# XMICRO-BP8.net
KiCad netlist of a schematic drawn in EAGLE
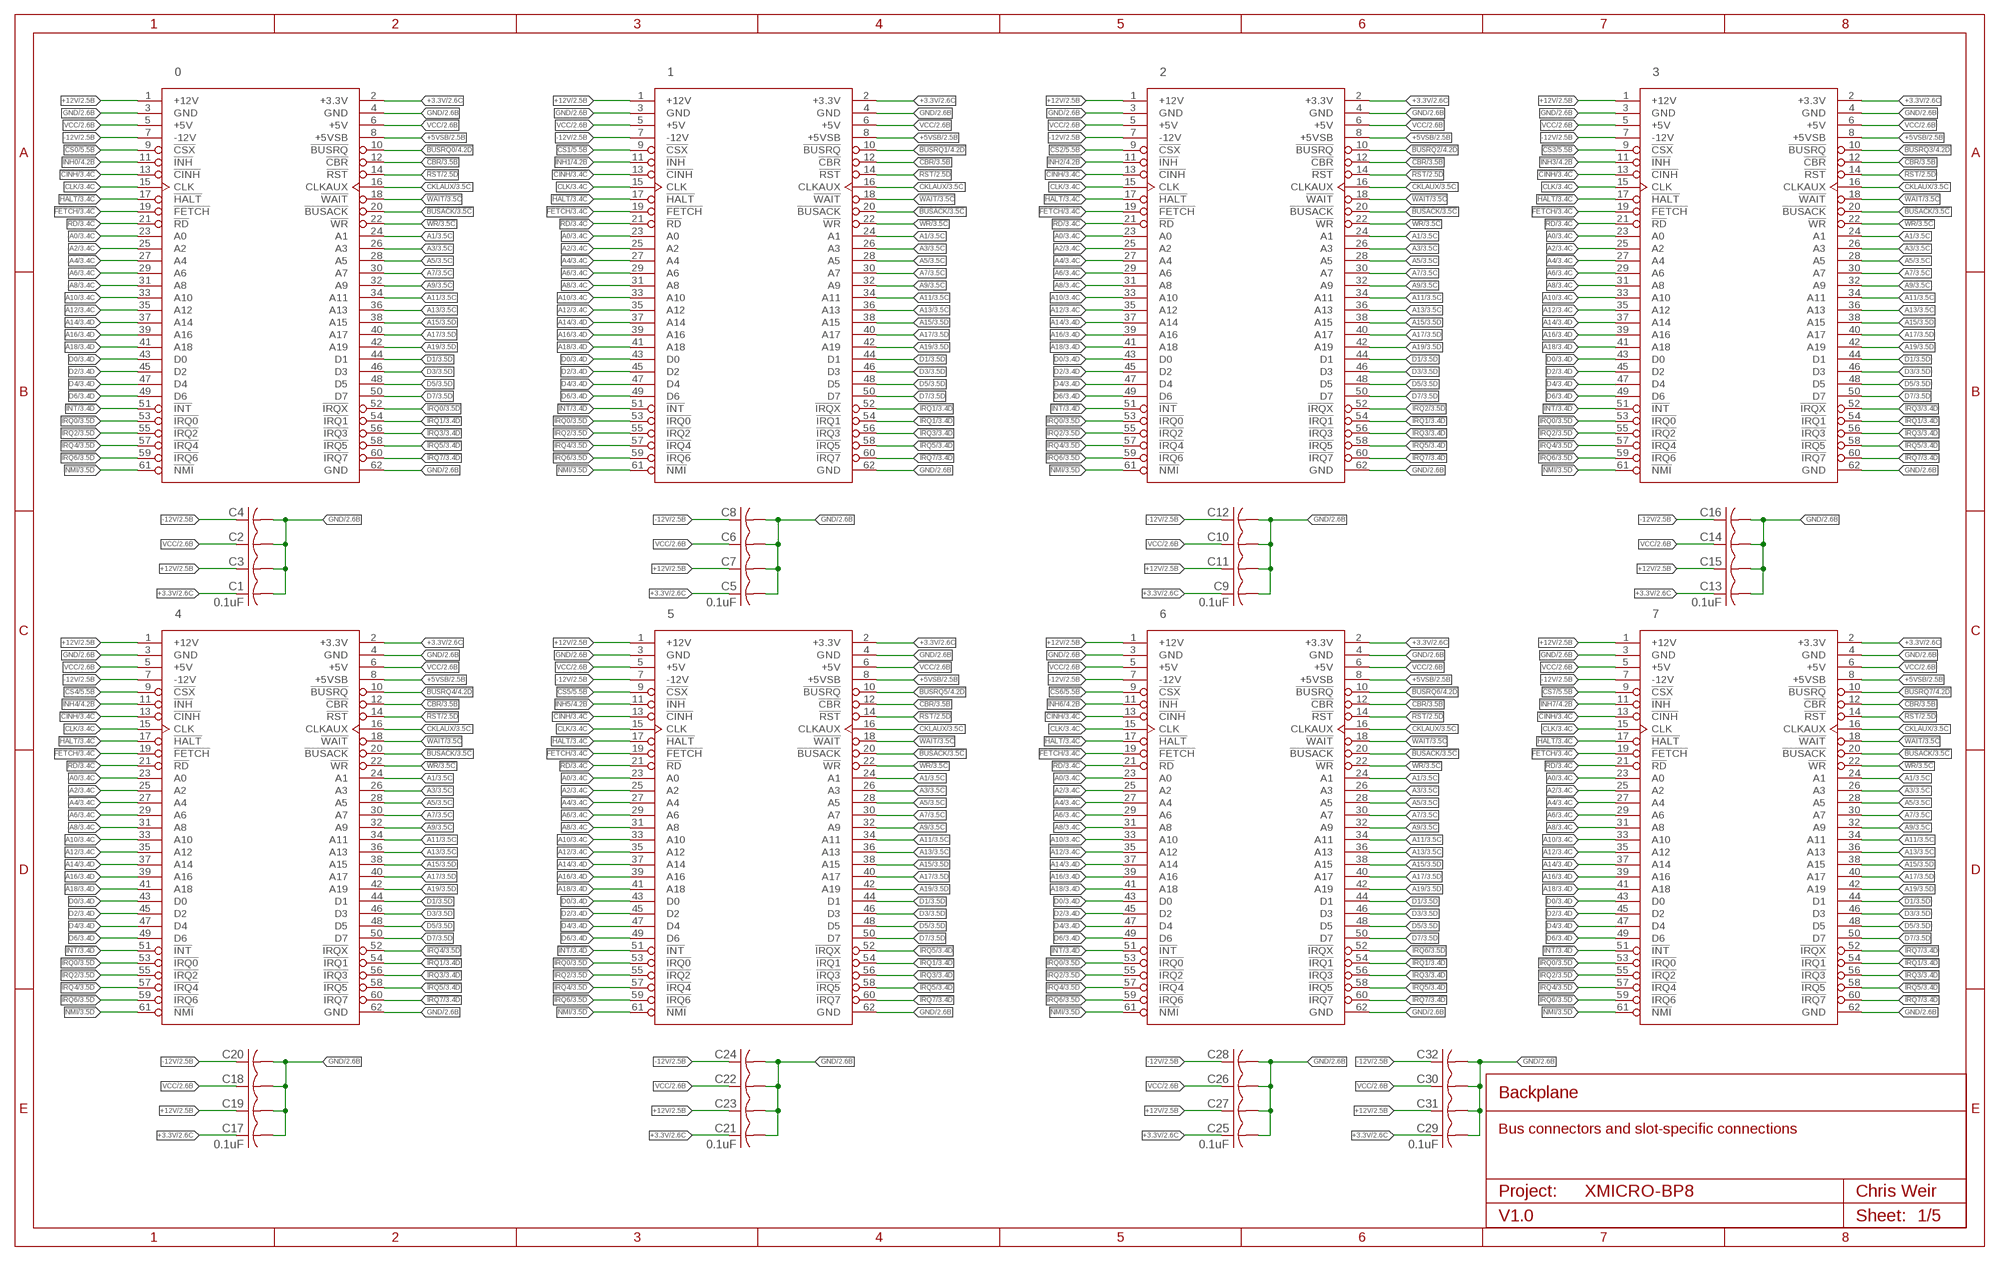
[diagram p0: schematic, sheet 1]
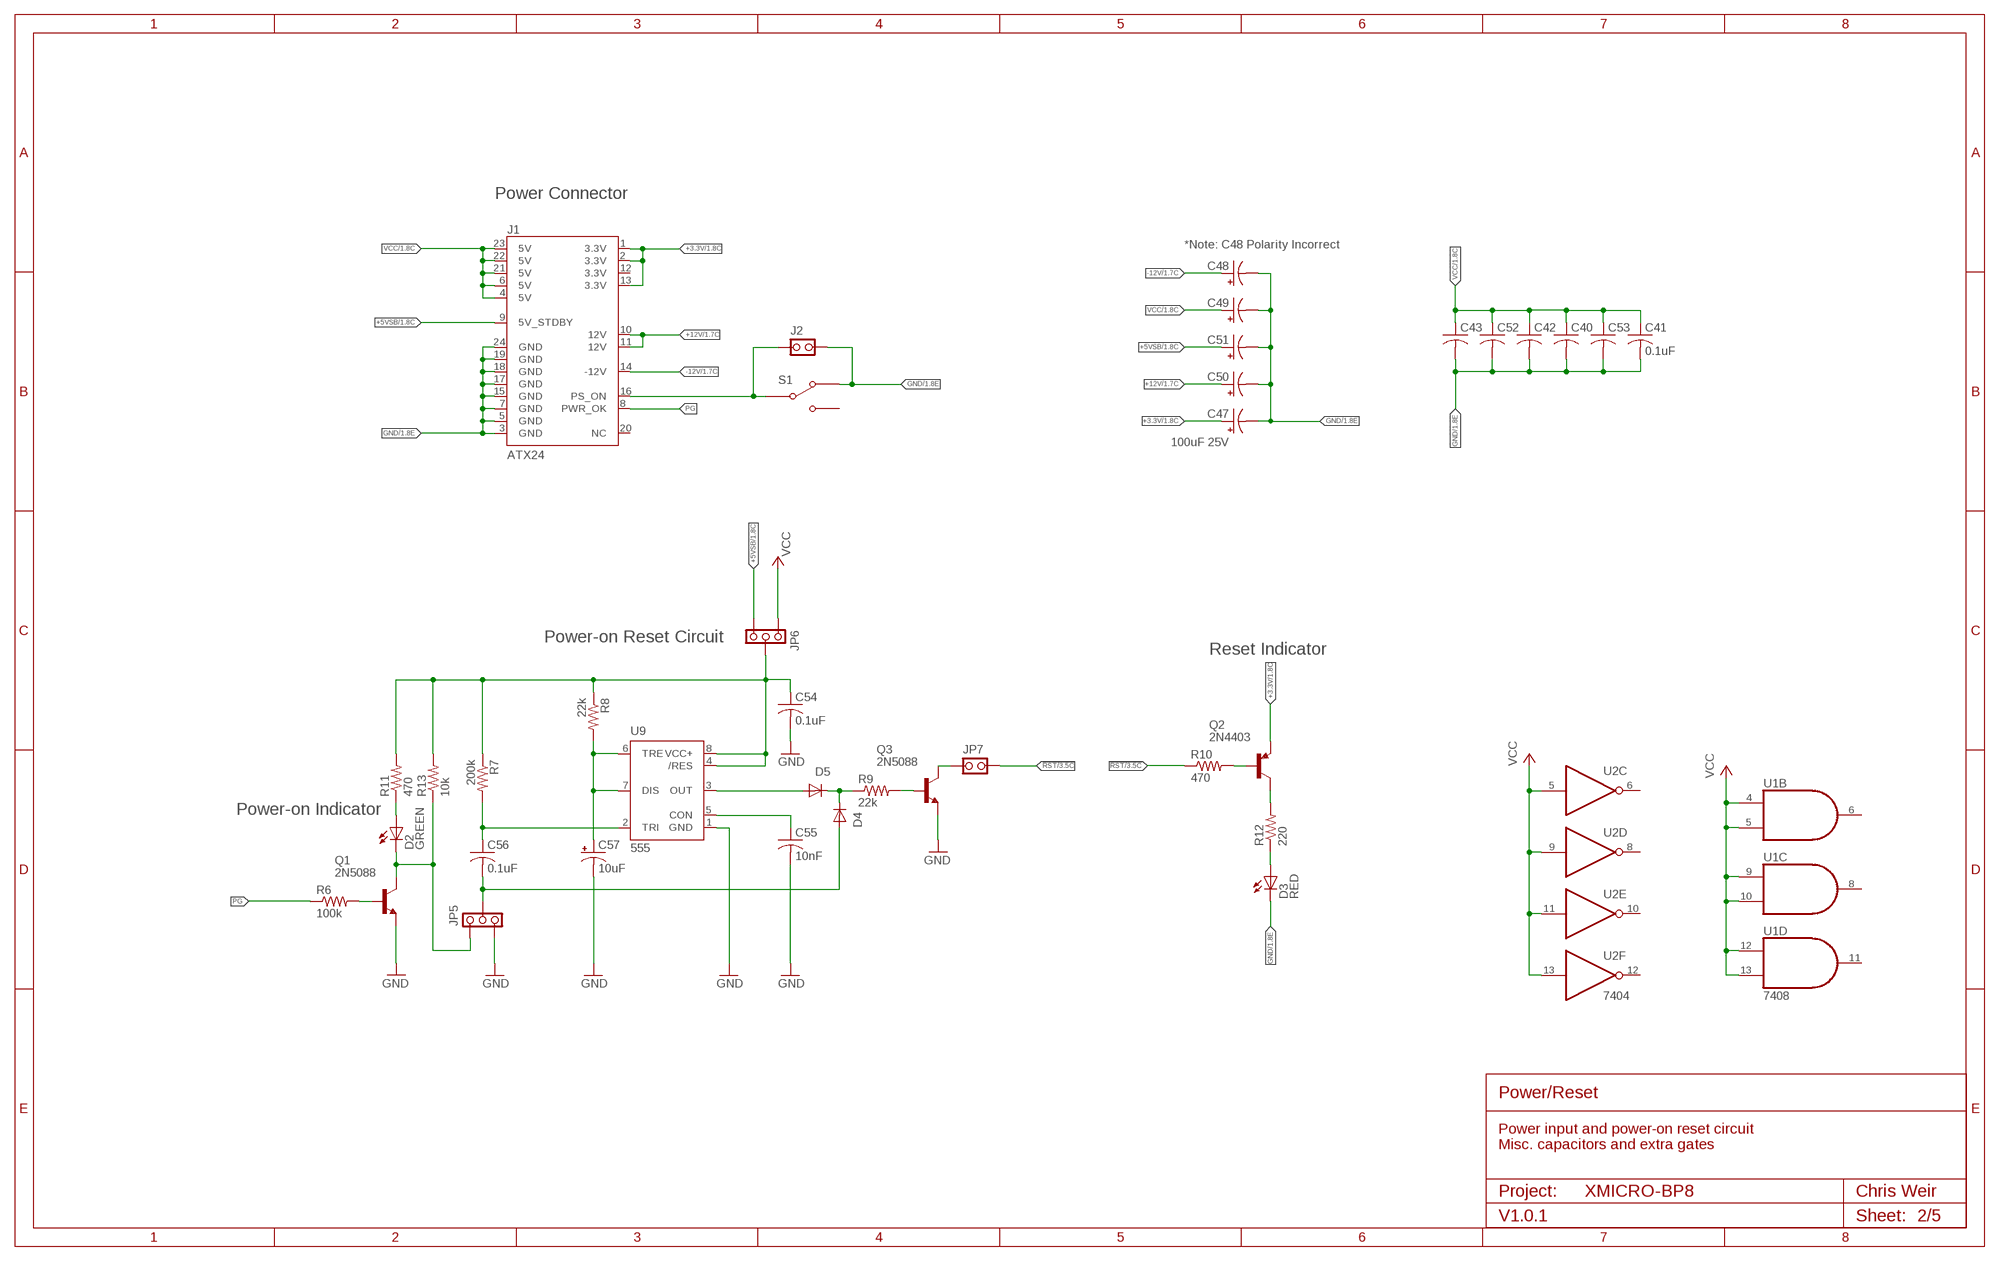
[diagram p1: schematic, sheet 2]
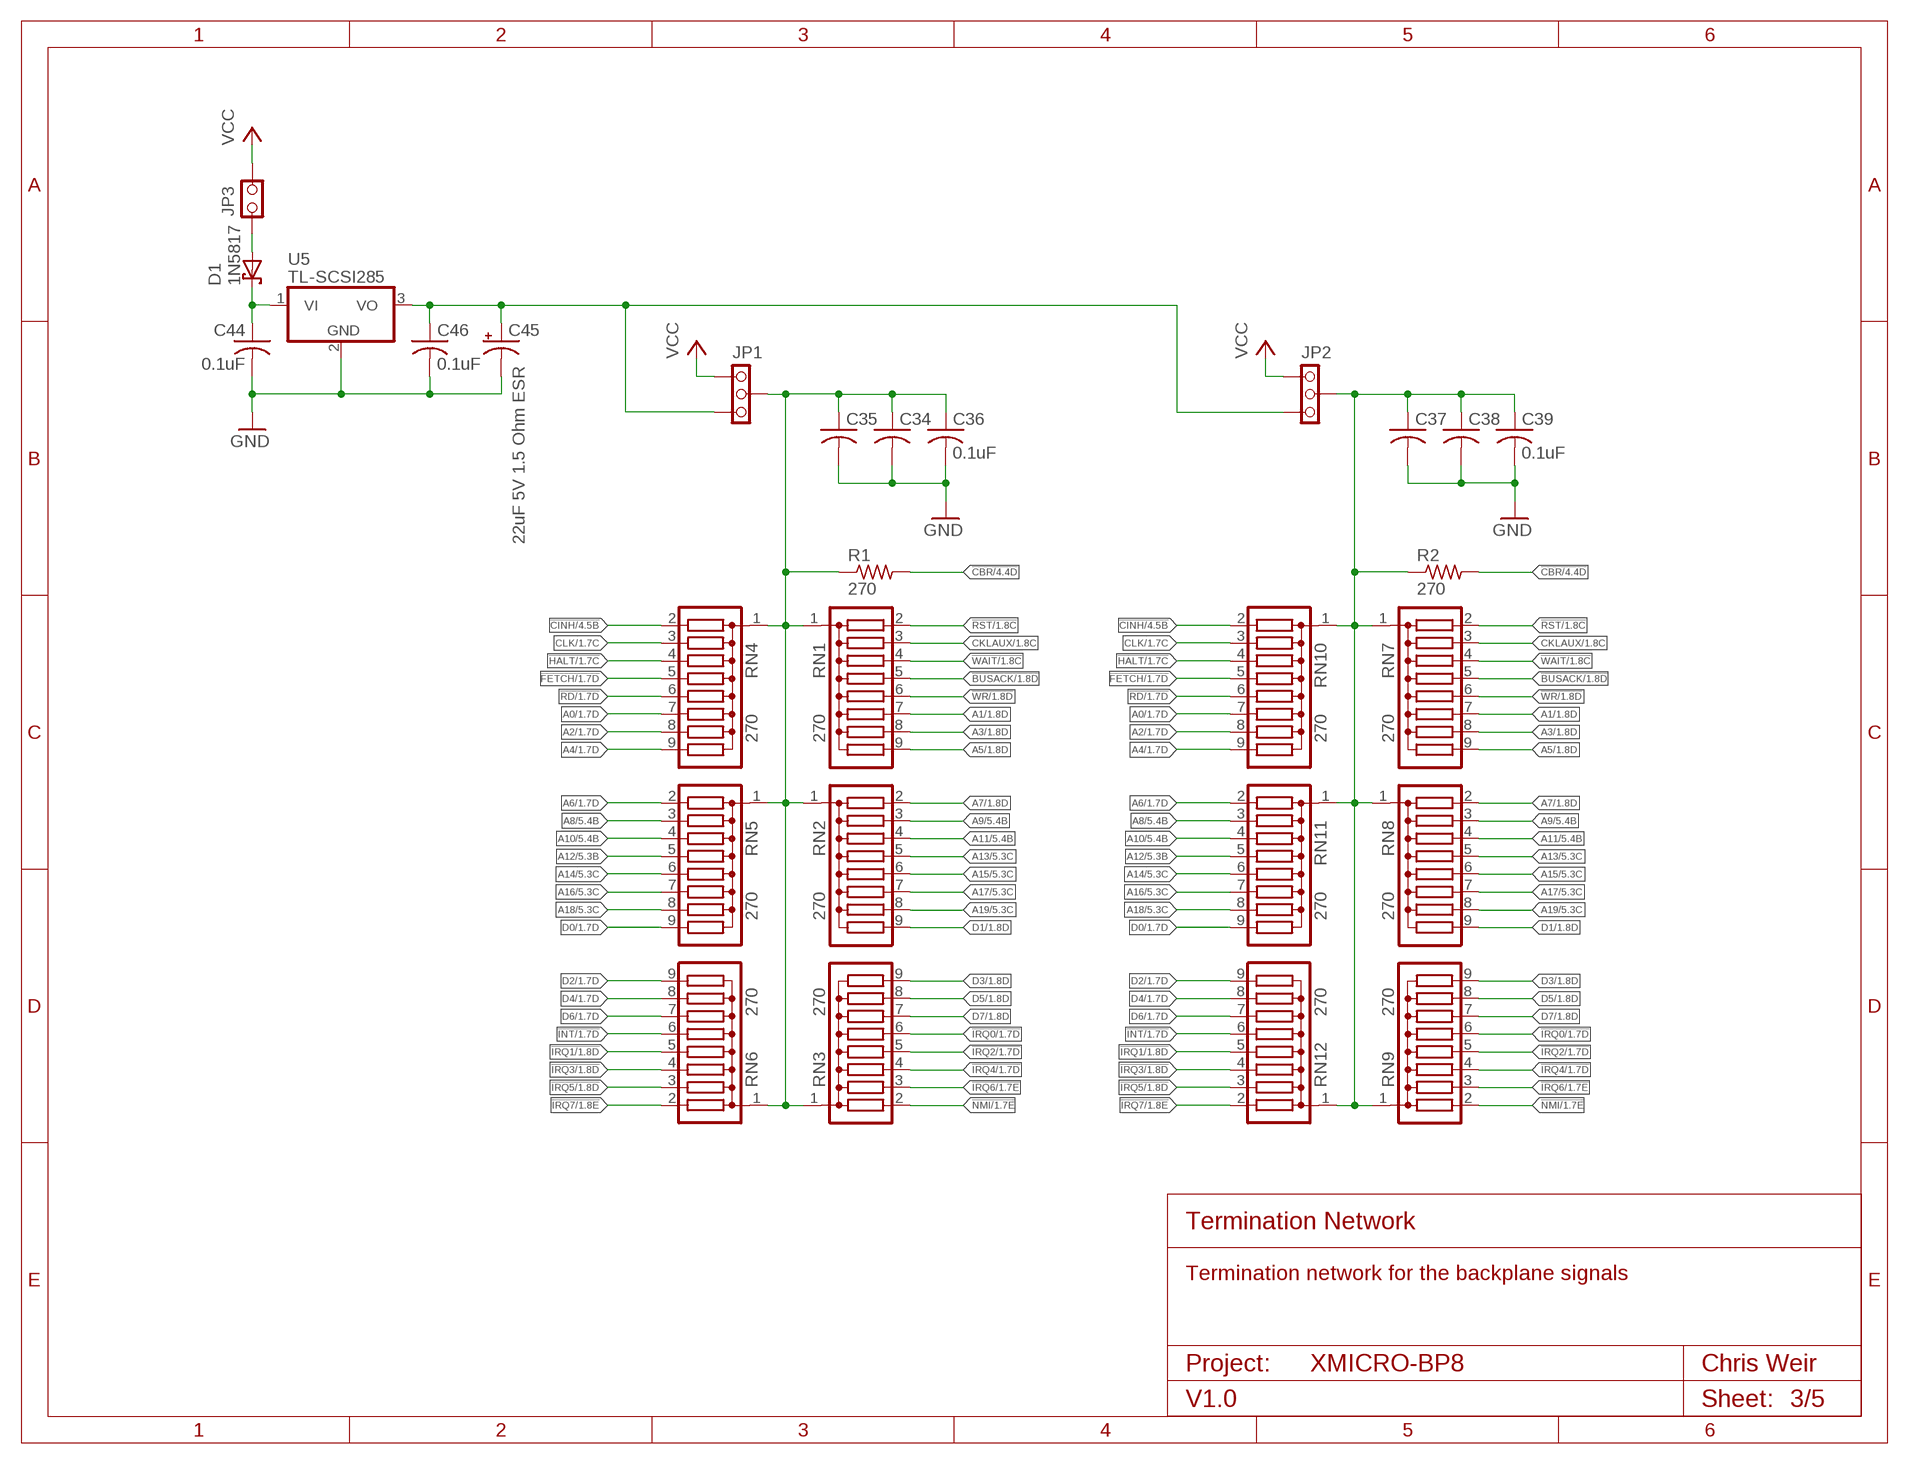
[diagram p2: schematic, sheet 3]
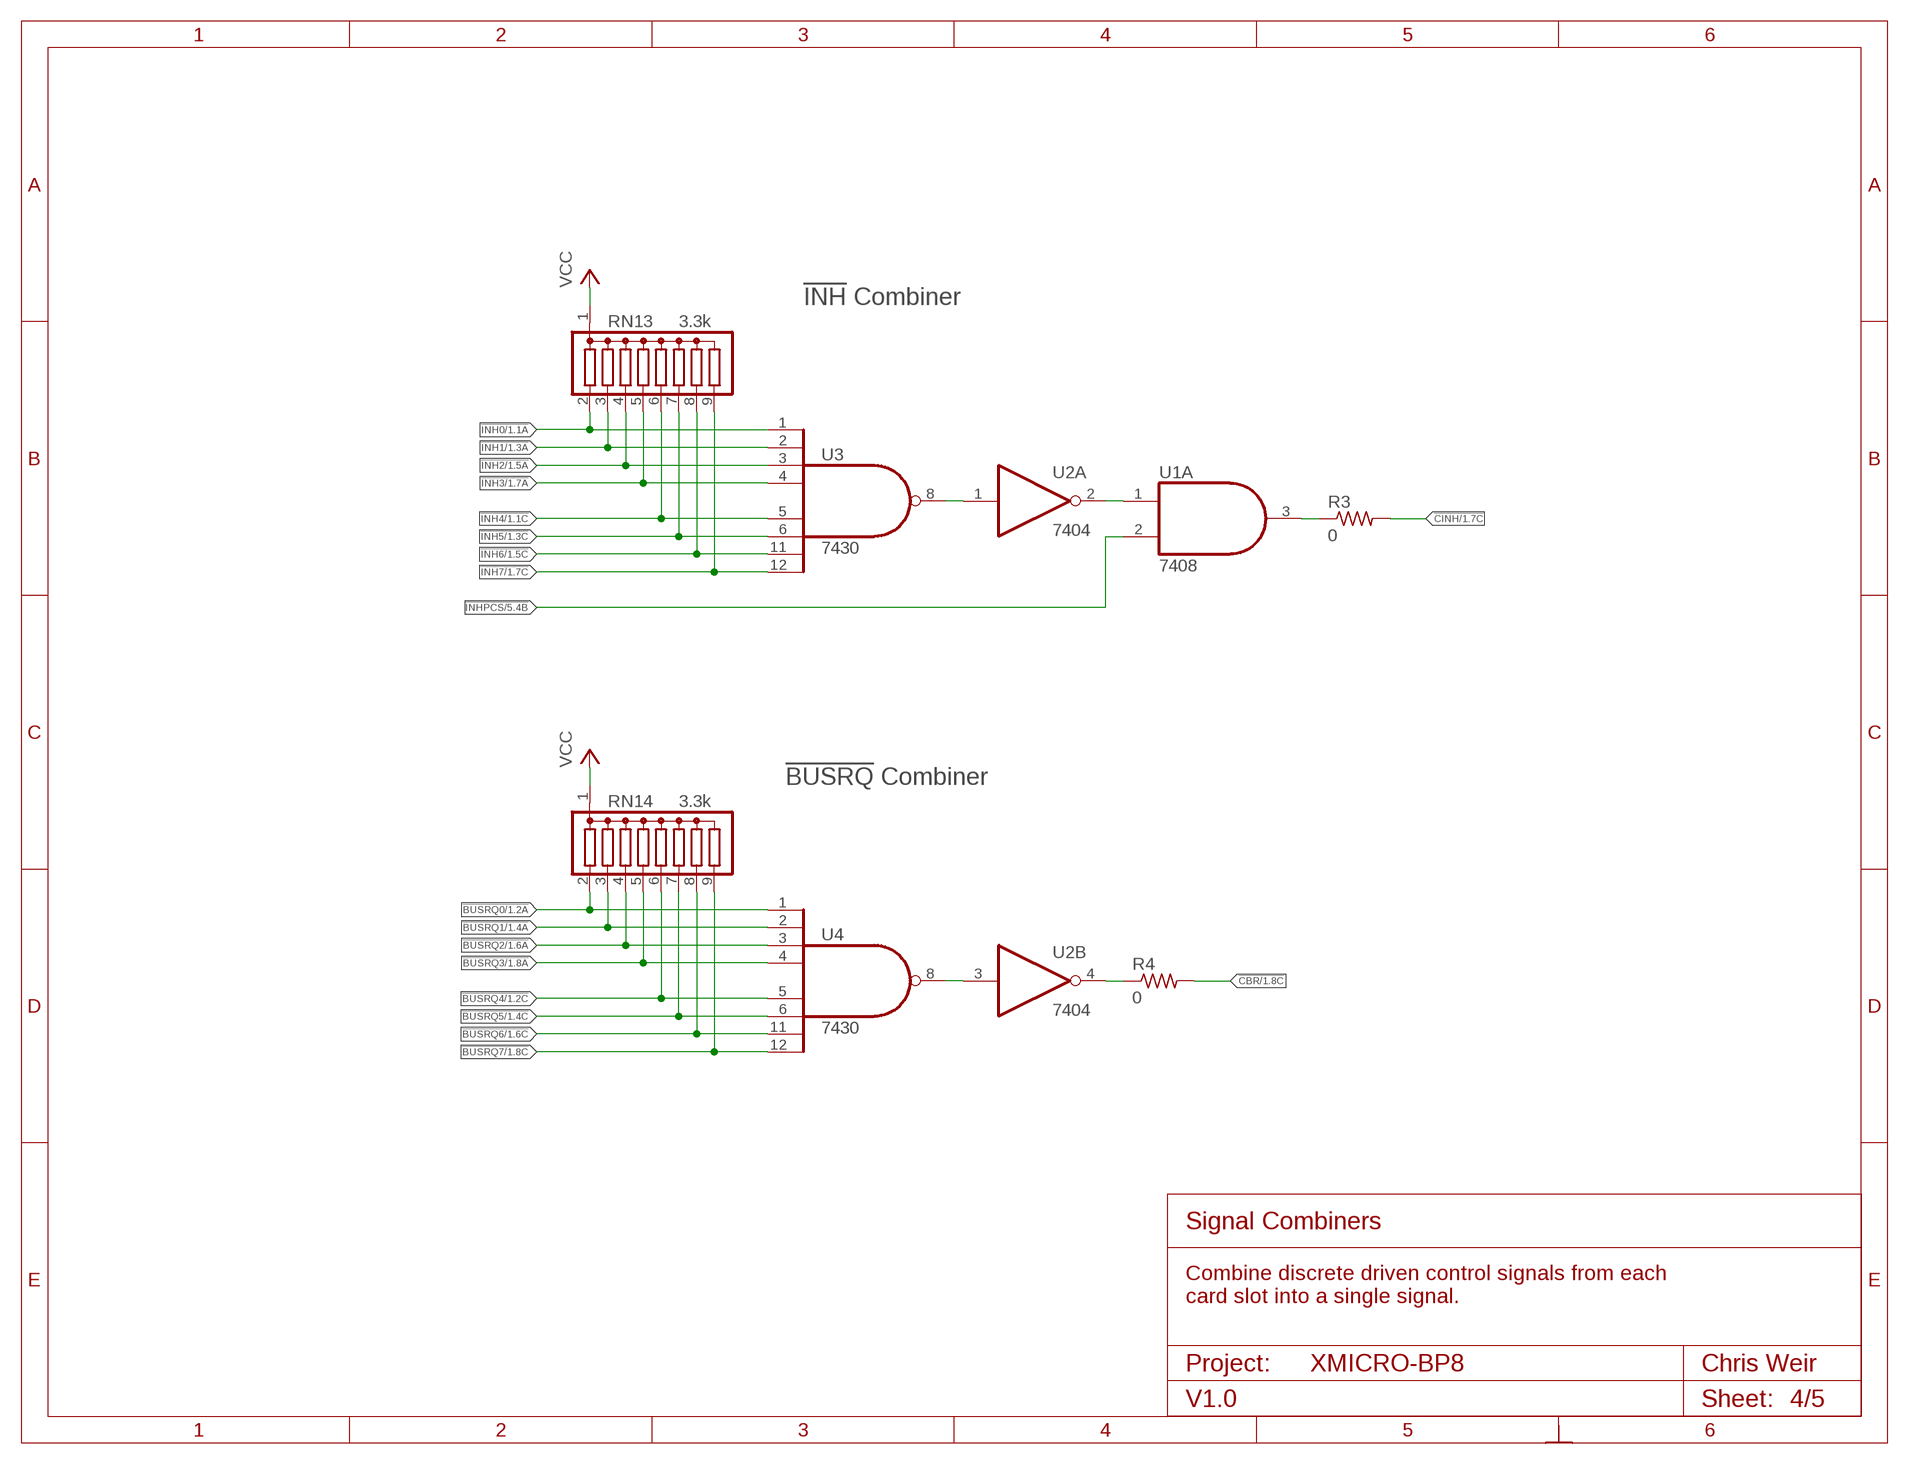
[diagram p3: schematic, sheet 4]
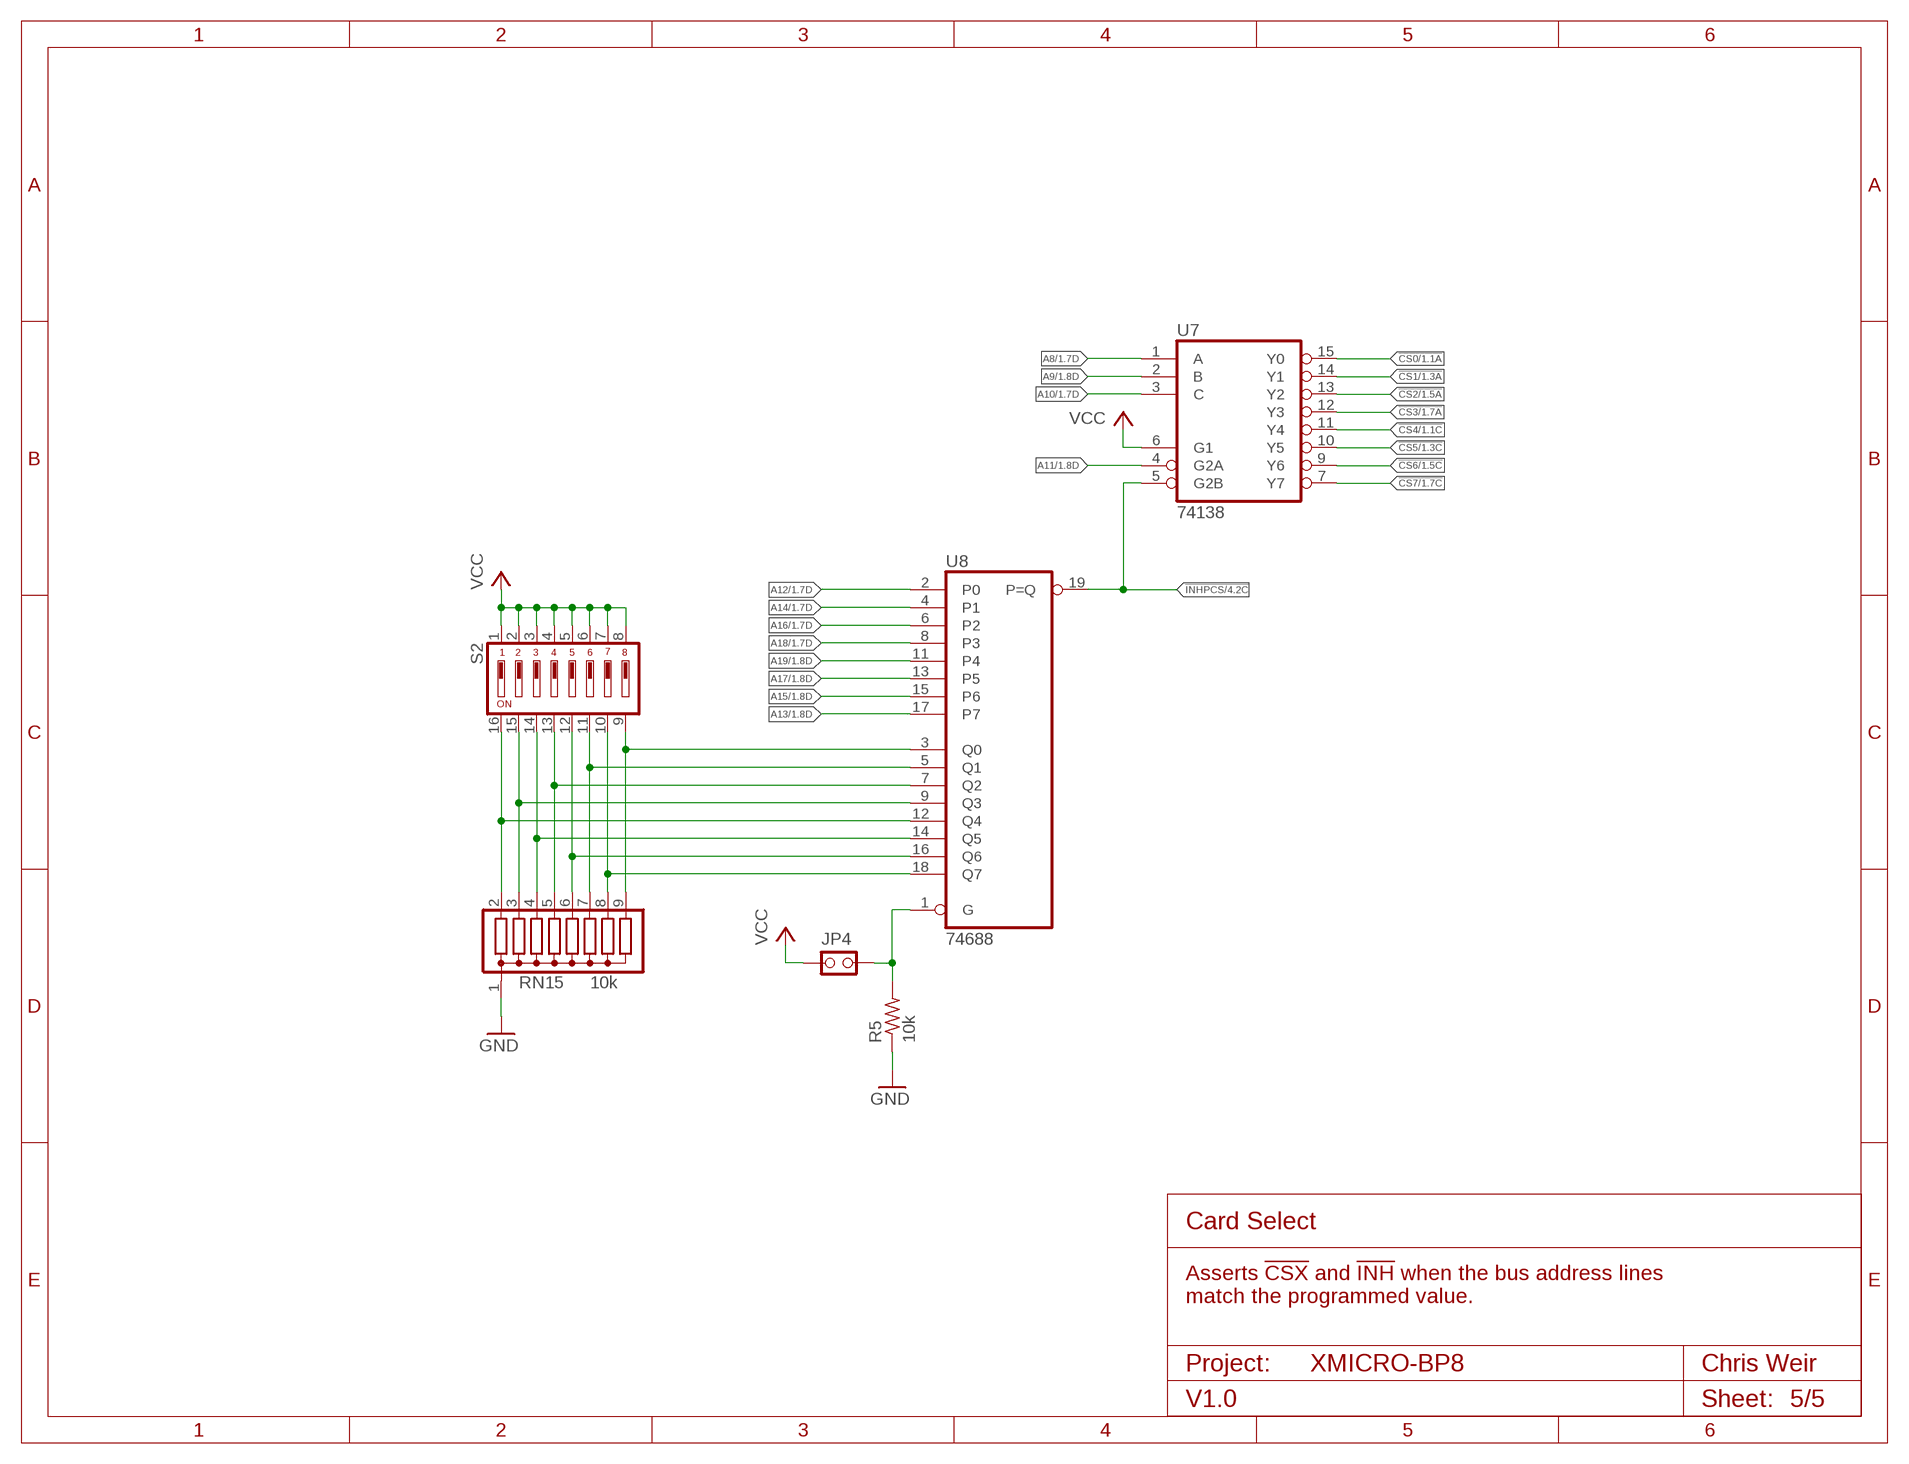
[diagram p4: schematic, sheet 5]

(export (version "E")
  (design (tool "Eeschema 10.0.6"))
  (components
    (comp (ref "C40")
      (value "0.1uF")
      (footprint "eagle-import:C025-024X044")
      (libsource (lib "eagle-import") (part "C-US025-024X044"))
    )
    (comp (ref "C41")
      (value "0.1uF")
      (footprint "eagle-import:C025-024X044")
      (libsource (lib "eagle-import") (part "C-US025-024X044"))
    )
    (comp (ref "C42")
      (value "0.1uF")
      (footprint "eagle-import:C025-024X044")
      (libsource (lib "eagle-import") (part "C-US025-024X044"))
    )
    (comp (ref "C43")
      (value "0.1uF")
      (footprint "eagle-import:C025-024X044")
      (libsource (lib "eagle-import") (part "C-US025-024X044"))
    )
    (comp (ref "C47")
      (value "100uF 25V")
      (footprint "eagle-import:C-10-5")
      (libsource (lib "eagle-import") (part "CPOL-US-10-5"))
    )
    (comp (ref "C48")
      (value "220uF 10V")
      (footprint "eagle-import:C-10-5")
      (libsource (lib "eagle-import") (part "CPOL-US-10-5"))
    )
    (comp (ref "C49")
      (value "220uF 10V")
      (footprint "eagle-import:C-10-5")
      (libsource (lib "eagle-import") (part "CPOL-US-10-5"))
    )
    (comp (ref "C50")
      (value "100uF 25V")
      (footprint "eagle-import:C-10-5")
      (libsource (lib "eagle-import") (part "CPOL-US-10-5"))
    )
    (comp (ref "C51")
      (value "220uF 10V")
      (footprint "eagle-import:C-10-5")
      (libsource (lib "eagle-import") (part "CPOL-US-10-5"))
    )
    (comp (ref "C52")
      (value "0.1uF")
      (footprint "eagle-import:C025-024X044")
      (libsource (lib "eagle-import") (part "C-US025-024X044"))
    )
    (comp (ref "C53")
      (value "0.1uF")
      (footprint "eagle-import:C025-024X044")
      (libsource (lib "eagle-import") (part "C-US025-024X044"))
    )
    (comp (ref "C54")
      (value "0.1uF")
      (footprint "eagle-import:C025-024X044")
      (libsource (lib "eagle-import") (part "C-US025-024X044"))
    )
    (comp (ref "C55")
      (value "10nF")
      (footprint "eagle-import:C025-024X044")
      (libsource (lib "eagle-import") (part "C-US025-024X044"))
    )
    (comp (ref "C56")
      (value "0.1uF")
      (footprint "eagle-import:C025-024X044")
      (libsource (lib "eagle-import") (part "C-US025-024X044"))
    )
    (comp (ref "C57")
      (value "10uF")
      (footprint "eagle-import:E2,5-7")
      (libsource (lib "eagle-import") (part "CPOL-USE2.5-7"))
    )
    (comp (ref "D2")
      (value "GREEN")
      (footprint "eagle-import:LED5MM")
      (libsource (lib "eagle-import") (part "LED5MM"))
    )
    (comp (ref "D3")
      (value "RED")
      (footprint "eagle-import:LED5MM")
      (libsource (lib "eagle-import") (part "LED5MM"))
    )
    (comp (ref "D4")
      (value "1N4148DO35-7")
      (footprint "eagle-import:DO35-7")
      (libsource (lib "eagle-import") (part "1N4148DO35-7"))
    )
    (comp (ref "D5")
      (value "1N4148DO35-7")
      (footprint "eagle-import:DO35-7")
      (libsource (lib "eagle-import") (part "1N4148DO35-7"))
    )
    (comp (ref "J1")
      (value "ATX24")
      (footprint "eagle-import:ATX24")
      (libsource (lib "eagle-import") (part "ATX24"))
    )
    (comp (ref "J2")
      (value "PINHD-1X2THRU")
      (footprint "eagle-import:1X02")
      (libsource (lib "eagle-import") (part "PINHD-1X2THRU"))
    )
    (comp (ref "JP5")
      (value "PINHD1X3THRU")
      (footprint "eagle-import:1X03")
      (libsource (lib "eagle-import") (part "PINHD1X3THRU"))
    )
    (comp (ref "JP6")
      (value "PINHD1X3THRU")
      (footprint "eagle-import:1X03")
      (libsource (lib "eagle-import") (part "PINHD1X3THRU"))
    )
    (comp (ref "JP7")
      (value "PINHD-1X2THRU")
      (footprint "eagle-import:1X02")
      (libsource (lib "eagle-import") (part "PINHD-1X2THRU"))
    )
    (comp (ref "Q1")
      (value "2N5088")
      (footprint "eagle-import:TO92")
      (libsource (lib "eagle-import") (part "TRANSISTOR-NPN-2N5088"))
    )
    (comp (ref "Q2")
      (value "2N4403")
      (footprint "eagle-import:TO92")
      (libsource (lib "eagle-import") (part "TRANSISTOR-PNP-2N4403"))
    )
    (comp (ref "Q3")
      (value "2N5088")
      (footprint "eagle-import:TO92")
      (libsource (lib "eagle-import") (part "TRANSISTOR-NPN-2N5088"))
    )
    (comp (ref "R6")
      (value "100k")
      (footprint "eagle-import:0207_10")
      (libsource (lib "eagle-import") (part "R-US_0207/10"))
    )
    (comp (ref "R7")
      (value "200k")
      (footprint "eagle-import:0207_10")
      (libsource (lib "eagle-import") (part "R-US_0207/10"))
    )
    (comp (ref "R8")
      (value "22k")
      (footprint "eagle-import:0207_10")
      (libsource (lib "eagle-import") (part "R-US_0207/10"))
    )
    (comp (ref "R9")
      (value "22k")
      (footprint "eagle-import:0207_10")
      (libsource (lib "eagle-import") (part "R-US_0207/10"))
    )
    (comp (ref "R10")
      (value "470")
      (footprint "eagle-import:0207_10")
      (libsource (lib "eagle-import") (part "R-US_0207/10"))
    )
    (comp (ref "R11")
      (value "470")
      (footprint "eagle-import:0207_10")
      (libsource (lib "eagle-import") (part "R-US_0207/10"))
    )
    (comp (ref "R12")
      (value "220")
      (footprint "eagle-import:0207_10")
      (libsource (lib "eagle-import") (part "R-US_0207/10"))
    )
    (comp (ref "R13")
      (value "10k")
      (footprint "eagle-import:0207_10")
      (libsource (lib "eagle-import") (part "R-US_0207/10"))
    )
    (comp (ref "S1")
      (value "SPDTT411013")
      (footprint "eagle-import:T411013")
      (libsource (lib "eagle-import") (part "SPDTT411013"))
    )
    (comp (ref "U1")
      (value "7408")
      (footprint "eagle-import:DIL14")
      (libsource (lib "eagle-import") (part "7408NLS"))
    )
    (comp (ref "U2")
      (value "7404")
      (footprint "eagle-import:DIL14")
      (libsource (lib "eagle-import") (part "7404NLS"))
    )
    (comp (ref "U9")
      (value "555")
      (footprint "eagle-import:DIL-08")
      (fields (field (name "MF") "Arrow Electronics") (field (name "MPN") "NE555N"))
      (libsource (lib "eagle-import") (part "NE555"))
    )
    (comp (ref "R3")
      (value "0")
      (footprint "eagle-import:0207_10")
      (libsource (lib "eagle-import") (part "R-US_0207/10"))
    )
    (comp (ref "R4")
      (value "0")
      (footprint "eagle-import:0207_10")
      (libsource (lib "eagle-import") (part "R-US_0207/10"))
    )
    (comp (ref "RN13")
      (value "3.3k")
      (footprint "eagle-import:SIL9")
      (fields (field (name "OC_FARNELL") "unknown") (field (name "OC_NEWARK") "unknown"))
      (libsource (lib "eagle-import") (part "G08R"))
    )
    (comp (ref "RN14")
      (value "3.3k")
      (footprint "eagle-import:SIL9")
      (fields (field (name "OC_FARNELL") "unknown") (field (name "OC_NEWARK") "unknown"))
      (libsource (lib "eagle-import") (part "G08R"))
    )
    (comp (ref "U3")
      (value "7430")
      (footprint "eagle-import:DIL14")
      (libsource (lib "eagle-import") (part "7430NLS"))
    )
    (comp (ref "U4")
      (value "7430")
      (footprint "eagle-import:DIL14")
      (libsource (lib "eagle-import") (part "7430NLS"))
    )
    (comp (ref "0")
      (value "XMICRO-BUS-PHYSICAL-EDGE62F")
      (footprint "eagle-import:EDGE62F")
      (libsource (lib "eagle-import") (part "XMICRO-BUS-PHYSICAL-EDGE62F"))
    )
    (comp (ref "1")
      (value "XMICRO-BUS-PHYSICAL-EDGE62F")
      (footprint "eagle-import:EDGE62F")
      (libsource (lib "eagle-import") (part "XMICRO-BUS-PHYSICAL-EDGE62F"))
    )
    (comp (ref "2")
      (value "XMICRO-BUS-PHYSICAL-EDGE62F")
      (footprint "eagle-import:EDGE62F")
      (libsource (lib "eagle-import") (part "XMICRO-BUS-PHYSICAL-EDGE62F"))
    )
    (comp (ref "3")
      (value "XMICRO-BUS-PHYSICAL-EDGE62F")
      (footprint "eagle-import:EDGE62F")
      (libsource (lib "eagle-import") (part "XMICRO-BUS-PHYSICAL-EDGE62F"))
    )
    (comp (ref "4")
      (value "XMICRO-BUS-PHYSICAL-EDGE62F")
      (footprint "eagle-import:EDGE62F")
      (libsource (lib "eagle-import") (part "XMICRO-BUS-PHYSICAL-EDGE62F"))
    )
    (comp (ref "5")
      (value "XMICRO-BUS-PHYSICAL-EDGE62F")
      (footprint "eagle-import:EDGE62F")
      (libsource (lib "eagle-import") (part "XMICRO-BUS-PHYSICAL-EDGE62F"))
    )
    (comp (ref "6")
      (value "XMICRO-BUS-PHYSICAL-EDGE62F")
      (footprint "eagle-import:EDGE62F")
      (libsource (lib "eagle-import") (part "XMICRO-BUS-PHYSICAL-EDGE62F"))
    )
    (comp (ref "7")
      (value "XMICRO-BUS-PHYSICAL-EDGE62F")
      (footprint "eagle-import:EDGE62F")
      (libsource (lib "eagle-import") (part "XMICRO-BUS-PHYSICAL-EDGE62F"))
    )
    (comp (ref "C1")
      (value "0.1uF")
      (footprint "eagle-import:C025-024X044")
      (libsource (lib "eagle-import") (part "C-US025-024X044"))
    )
    (comp (ref "C2")
      (value "0.1uF")
      (footprint "eagle-import:C025-024X044")
      (libsource (lib "eagle-import") (part "C-US025-024X044"))
    )
    (comp (ref "C3")
      (value "0.1uF")
      (footprint "eagle-import:C025-024X044")
      (libsource (lib "eagle-import") (part "C-US025-024X044"))
    )
    (comp (ref "C4")
      (value "0.1uF")
      (footprint "eagle-import:C050-024X044")
      (libsource (lib "eagle-import") (part "C-US050-024X044"))
    )
    (comp (ref "C5")
      (value "0.1uF")
      (footprint "eagle-import:C025-024X044")
      (libsource (lib "eagle-import") (part "C-US025-024X044"))
    )
    (comp (ref "C6")
      (value "0.1uF")
      (footprint "eagle-import:C025-024X044")
      (libsource (lib "eagle-import") (part "C-US025-024X044"))
    )
    (comp (ref "C7")
      (value "0.1uF")
      (footprint "eagle-import:C025-024X044")
      (libsource (lib "eagle-import") (part "C-US025-024X044"))
    )
    (comp (ref "C8")
      (value "0.1uF")
      (footprint "eagle-import:C050-024X044")
      (libsource (lib "eagle-import") (part "C-US050-024X044"))
    )
    (comp (ref "C9")
      (value "0.1uF")
      (footprint "eagle-import:C025-024X044")
      (libsource (lib "eagle-import") (part "C-US025-024X044"))
    )
    (comp (ref "C10")
      (value "0.1uF")
      (footprint "eagle-import:C025-024X044")
      (libsource (lib "eagle-import") (part "C-US025-024X044"))
    )
    (comp (ref "C11")
      (value "0.1uF")
      (footprint "eagle-import:C025-024X044")
      (libsource (lib "eagle-import") (part "C-US025-024X044"))
    )
    (comp (ref "C12")
      (value "0.1uF")
      (footprint "eagle-import:C050-024X044")
      (libsource (lib "eagle-import") (part "C-US050-024X044"))
    )
    (comp (ref "C13")
      (value "0.1uF")
      (footprint "eagle-import:C025-024X044")
      (libsource (lib "eagle-import") (part "C-US025-024X044"))
    )
    (comp (ref "C14")
      (value "0.1uF")
      (footprint "eagle-import:C025-024X044")
      (libsource (lib "eagle-import") (part "C-US025-024X044"))
    )
    (comp (ref "C15")
      (value "0.1uF")
      (footprint "eagle-import:C025-024X044")
      (libsource (lib "eagle-import") (part "C-US025-024X044"))
    )
    (comp (ref "C16")
      (value "0.1uF")
      (footprint "eagle-import:C050-024X044")
      (libsource (lib "eagle-import") (part "C-US050-024X044"))
    )
    (comp (ref "C17")
      (value "0.1uF")
      (footprint "eagle-import:C025-024X044")
      (libsource (lib "eagle-import") (part "C-US025-024X044"))
    )
    (comp (ref "C18")
      (value "0.1uF")
      (footprint "eagle-import:C025-024X044")
      (libsource (lib "eagle-import") (part "C-US025-024X044"))
    )
    (comp (ref "C19")
      (value "0.1uF")
      (footprint "eagle-import:C025-024X044")
      (libsource (lib "eagle-import") (part "C-US025-024X044"))
    )
    (comp (ref "C20")
      (value "0.1uF")
      (footprint "eagle-import:C050-024X044")
      (libsource (lib "eagle-import") (part "C-US050-024X044"))
    )
    (comp (ref "C21")
      (value "0.1uF")
      (footprint "eagle-import:C025-024X044")
      (libsource (lib "eagle-import") (part "C-US025-024X044"))
    )
    (comp (ref "C22")
      (value "0.1uF")
      (footprint "eagle-import:C025-024X044")
      (libsource (lib "eagle-import") (part "C-US025-024X044"))
    )
    (comp (ref "C23")
      (value "0.1uF")
      (footprint "eagle-import:C025-024X044")
      (libsource (lib "eagle-import") (part "C-US025-024X044"))
    )
    (comp (ref "C24")
      (value "0.1uF")
      (footprint "eagle-import:C050-024X044")
      (libsource (lib "eagle-import") (part "C-US050-024X044"))
    )
    (comp (ref "C25")
      (value "0.1uF")
      (footprint "eagle-import:C025-024X044")
      (libsource (lib "eagle-import") (part "C-US025-024X044"))
    )
    (comp (ref "C26")
      (value "0.1uF")
      (footprint "eagle-import:C025-024X044")
      (libsource (lib "eagle-import") (part "C-US025-024X044"))
    )
    (comp (ref "C27")
      (value "0.1uF")
      (footprint "eagle-import:C025-024X044")
      (libsource (lib "eagle-import") (part "C-US025-024X044"))
    )
    (comp (ref "C28")
      (value "0.1uF")
      (footprint "eagle-import:C050-024X044")
      (libsource (lib "eagle-import") (part "C-US050-024X044"))
    )
    (comp (ref "C29")
      (value "0.1uF")
      (footprint "eagle-import:C025-024X044")
      (libsource (lib "eagle-import") (part "C-US025-024X044"))
    )
    (comp (ref "C30")
      (value "0.1uF")
      (footprint "eagle-import:C025-024X044")
      (libsource (lib "eagle-import") (part "C-US025-024X044"))
    )
    (comp (ref "C31")
      (value "0.1uF")
      (footprint "eagle-import:C025-024X044")
      (libsource (lib "eagle-import") (part "C-US025-024X044"))
    )
    (comp (ref "C32")
      (value "0.1uF")
      (footprint "eagle-import:C025-024X044")
      (libsource (lib "eagle-import") (part "C-US025-024X044"))
    )
    (comp (ref "C34")
      (value "0.1uF")
      (footprint "eagle-import:C025-024X044")
      (libsource (lib "eagle-import") (part "C-US025-024X044"))
    )
    (comp (ref "C35")
      (value "0.1uF")
      (footprint "eagle-import:C025-024X044")
      (libsource (lib "eagle-import") (part "C-US025-024X044"))
    )
    (comp (ref "C36")
      (value "0.1uF")
      (footprint "eagle-import:C025-024X044")
      (libsource (lib "eagle-import") (part "C-US025-024X044"))
    )
    (comp (ref "C37")
      (value "0.1uF")
      (footprint "eagle-import:C025-024X044")
      (libsource (lib "eagle-import") (part "C-US025-024X044"))
    )
    (comp (ref "C38")
      (value "0.1uF")
      (footprint "eagle-import:C025-024X044")
      (libsource (lib "eagle-import") (part "C-US025-024X044"))
    )
    (comp (ref "C39")
      (value "0.1uF")
      (footprint "eagle-import:C025-024X044")
      (libsource (lib "eagle-import") (part "C-US025-024X044"))
    )
    (comp (ref "C44")
      (value "0.1uF")
      (footprint "eagle-import:C025-024X044")
      (libsource (lib "eagle-import") (part "C-US025-024X044"))
    )
    (comp (ref "C45")
      (value "22uF 5V 1.5 Ohm ESR")
      (footprint "eagle-import:E2,5-7")
      (libsource (lib "eagle-import") (part "CPOL-USE2.5-7"))
    )
    (comp (ref "C46")
      (value "0.1uF")
      (footprint "eagle-import:C050-024X044")
      (libsource (lib "eagle-import") (part "C-US050-024X044"))
    )
    (comp (ref "D1")
      (value "1N5817")
      (footprint "eagle-import:DO41-7.6")
      (libsource (lib "eagle-import") (part "1N5817-B"))
    )
    (comp (ref "JP1")
      (value "PINHD1X3THRU")
      (footprint "eagle-import:1X03")
      (libsource (lib "eagle-import") (part "PINHD1X3THRU"))
    )
    (comp (ref "JP2")
      (value "PINHD1X3THRU")
      (footprint "eagle-import:1X03")
      (libsource (lib "eagle-import") (part "PINHD1X3THRU"))
    )
    (comp (ref "JP3")
      (value "PINHD-1X2THRU")
      (footprint "eagle-import:1X02")
      (libsource (lib "eagle-import") (part "PINHD-1X2THRU"))
    )
    (comp (ref "R1")
      (value "270")
      (footprint "eagle-import:0207_10")
      (libsource (lib "eagle-import") (part "R-US_0207/10"))
    )
    (comp (ref "R2")
      (value "270")
      (footprint "eagle-import:0207_10")
      (libsource (lib "eagle-import") (part "R-US_0207/10"))
    )
    (comp (ref "RN1")
      (value "270")
      (footprint "eagle-import:SIL9")
      (fields (field (name "OC_FARNELL") "unknown") (field (name "OC_NEWARK") "unknown"))
      (libsource (lib "eagle-import") (part "G08R"))
    )
    (comp (ref "RN2")
      (value "270")
      (footprint "eagle-import:SIL9")
      (fields (field (name "OC_FARNELL") "unknown") (field (name "OC_NEWARK") "unknown"))
      (libsource (lib "eagle-import") (part "G08R"))
    )
    (comp (ref "RN3")
      (value "270")
      (footprint "eagle-import:SIL9")
      (fields (field (name "OC_FARNELL") "unknown") (field (name "OC_NEWARK") "unknown"))
      (libsource (lib "eagle-import") (part "G08R"))
    )
    (comp (ref "RN4")
      (value "270")
      (footprint "eagle-import:SIL9")
      (fields (field (name "OC_FARNELL") "unknown") (field (name "OC_NEWARK") "unknown"))
      (libsource (lib "eagle-import") (part "G08R"))
    )
    (comp (ref "RN5")
      (value "270")
      (footprint "eagle-import:SIL9")
      (fields (field (name "OC_FARNELL") "unknown") (field (name "OC_NEWARK") "unknown"))
      (libsource (lib "eagle-import") (part "G08R"))
    )
    (comp (ref "RN6")
      (value "270")
      (footprint "eagle-import:SIL9")
      (fields (field (name "OC_FARNELL") "unknown") (field (name "OC_NEWARK") "unknown"))
      (libsource (lib "eagle-import") (part "G08R"))
    )
    (comp (ref "RN7")
      (value "270")
      (footprint "eagle-import:SIL9")
      (fields (field (name "OC_FARNELL") "unknown") (field (name "OC_NEWARK") "unknown"))
      (libsource (lib "eagle-import") (part "G08R"))
    )
    (comp (ref "RN8")
      (value "270")
      (footprint "eagle-import:SIL9")
      (fields (field (name "OC_FARNELL") "unknown") (field (name "OC_NEWARK") "unknown"))
      (libsource (lib "eagle-import") (part "G08R"))
    )
    (comp (ref "RN9")
      (value "270")
      (footprint "eagle-import:SIL9")
      (fields (field (name "OC_FARNELL") "unknown") (field (name "OC_NEWARK") "unknown"))
      (libsource (lib "eagle-import") (part "G08R"))
    )
    (comp (ref "RN10")
      (value "270")
      (footprint "eagle-import:SIL9")
      (fields (field (name "OC_FARNELL") "unknown") (field (name "OC_NEWARK") "unknown"))
      (libsource (lib "eagle-import") (part "G08R"))
    )
    (comp (ref "RN11")
      (value "270")
      (footprint "eagle-import:SIL9")
      (fields (field (name "OC_FARNELL") "unknown") (field (name "OC_NEWARK") "unknown"))
      (libsource (lib "eagle-import") (part "G08R"))
    )
    (comp (ref "RN12")
      (value "270")
      (footprint "eagle-import:SIL9")
      (fields (field (name "OC_FARNELL") "unknown") (field (name "OC_NEWARK") "unknown"))
      (libsource (lib "eagle-import") (part "G08R"))
    )
    (comp (ref "U5")
      (value "TL-SCSI285")
      (footprint "eagle-import:TO220H")
      (libsource (lib "eagle-import") (part "TL-SCSI285-TO220H"))
    )
    (comp (ref "JP4")
      (value "PINHD-1X2THRU")
      (footprint "eagle-import:1X02")
      (libsource (lib "eagle-import") (part "PINHD-1X2THRU"))
    )
    (comp (ref "R5")
      (value "10k")
      (footprint "eagle-import:0207_10")
      (libsource (lib "eagle-import") (part "R-US_0207/10"))
    )
    (comp (ref "RN15")
      (value "10k")
      (footprint "eagle-import:SIL9")
      (fields (field (name "OC_FARNELL") "unknown") (field (name "OC_NEWARK") "unknown"))
      (libsource (lib "eagle-import") (part "G08R"))
    )
    (comp (ref "S2")
      (value "SW-DIP08")
      (footprint "eagle-import:SW-DIP8")
      (libsource (lib "eagle-import") (part "SW-DIP08"))
    )
    (comp (ref "U7")
      (value "74138")
      (footprint "eagle-import:DIL16")
      (libsource (lib "eagle-import") (part "74138NLS"))
    )
    (comp (ref "U8")
      (value "74688")
      (footprint "eagle-import:DIL20")
      (libsource (lib "eagle-import") (part "74688NLS"))
    )
  )
  (nets
    (net (code "1") (name "+3.3V") (class "Default")
      (node (ref "0") (pin "2") (pinfunction "+3.3V_2") (pintype "bidirectional"))
      (node (ref "1") (pin "2") (pinfunction "+3.3V_2") (pintype "bidirectional"))
      (node (ref "2") (pin "2") (pinfunction "+3.3V_2") (pintype "bidirectional"))
      (node (ref "3") (pin "2") (pinfunction "+3.3V_2") (pintype "bidirectional"))
      (node (ref "4") (pin "2") (pinfunction "+3.3V_2") (pintype "bidirectional"))
      (node (ref "5") (pin "2") (pinfunction "+3.3V_2") (pintype "bidirectional"))
      (node (ref "6") (pin "2") (pinfunction "+3.3V_2") (pintype "bidirectional"))
      (node (ref "7") (pin "2") (pinfunction "+3.3V_2") (pintype "bidirectional"))
      (node (ref "C1") (pin "1") (pinfunction "1_1") (pintype "passive"))
      (node (ref "C13") (pin "1") (pinfunction "1_1") (pintype "passive"))
      (node (ref "C17") (pin "1") (pinfunction "1_1") (pintype "passive"))
      (node (ref "C21") (pin "1") (pinfunction "1_1") (pintype "passive"))
      (node (ref "C25") (pin "1") (pinfunction "1_1") (pintype "passive"))
      (node (ref "C29") (pin "1") (pinfunction "1_1") (pintype "passive"))
      (node (ref "C47") (pin "+") (pinfunction "+_+") (pintype "passive"))
      (node (ref "C5") (pin "1") (pinfunction "1_1") (pintype "passive"))
      (node (ref "C9") (pin "1") (pinfunction "1_1") (pintype "passive"))
      (node (ref "J1") (pin "1") (pinfunction "3.3V_1") (pintype "bidirectional"))
      (node (ref "J1") (pin "13") (pinfunction "3.3V_13") (pintype "bidirectional"))
      (node (ref "J1") (pin "2") (pinfunction "3.3V_2") (pintype "bidirectional"))
      (node (ref "Q2") (pin "1") (pinfunction "E_1") (pintype "passive"))
    )
    (net (code "2") (name "+5VSB") (class "Default")
      (node (ref "0") (pin "8") (pinfunction "+5VSB_8") (pintype "bidirectional"))
      (node (ref "1") (pin "8") (pinfunction "+5VSB_8") (pintype "bidirectional"))
      (node (ref "2") (pin "8") (pinfunction "+5VSB_8") (pintype "bidirectional"))
      (node (ref "3") (pin "8") (pinfunction "+5VSB_8") (pintype "bidirectional"))
      (node (ref "4") (pin "8") (pinfunction "+5VSB_8") (pintype "bidirectional"))
      (node (ref "5") (pin "8") (pinfunction "+5VSB_8") (pintype "bidirectional"))
      (node (ref "6") (pin "8") (pinfunction "+5VSB_8") (pintype "bidirectional"))
      (node (ref "7") (pin "8") (pinfunction "+5VSB_8") (pintype "bidirectional"))
      (node (ref "C51") (pin "+") (pinfunction "+_+") (pintype "passive"))
      (node (ref "J1") (pin "9") (pinfunction "5V_STDBY_9") (pintype "bidirectional"))
      (node (ref "JP6") (pin "3") (pinfunction "3_3") (pintype "passive"))
    )
    (net (code "3") (name "+12V") (class "Default")
      (node (ref "0") (pin "1") (pinfunction "+12V_1") (pintype "bidirectional"))
      (node (ref "1") (pin "1") (pinfunction "+12V_1") (pintype "bidirectional"))
      (node (ref "2") (pin "1") (pinfunction "+12V_1") (pintype "bidirectional"))
      (node (ref "3") (pin "1") (pinfunction "+12V_1") (pintype "bidirectional"))
      (node (ref "4") (pin "1") (pinfunction "+12V_1") (pintype "bidirectional"))
      (node (ref "5") (pin "1") (pinfunction "+12V_1") (pintype "bidirectional"))
      (node (ref "6") (pin "1") (pinfunction "+12V_1") (pintype "bidirectional"))
      (node (ref "7") (pin "1") (pinfunction "+12V_1") (pintype "bidirectional"))
      (node (ref "C11") (pin "1") (pinfunction "1_1") (pintype "passive"))
      (node (ref "C15") (pin "1") (pinfunction "1_1") (pintype "passive"))
      (node (ref "C19") (pin "1") (pinfunction "1_1") (pintype "passive"))
      (node (ref "C23") (pin "1") (pinfunction "1_1") (pintype "passive"))
      (node (ref "C27") (pin "1") (pinfunction "1_1") (pintype "passive"))
      (node (ref "C3") (pin "1") (pinfunction "1_1") (pintype "passive"))
      (node (ref "C31") (pin "1") (pinfunction "1_1") (pintype "passive"))
      (node (ref "C50") (pin "+") (pinfunction "+_+") (pintype "passive"))
      (node (ref "C7") (pin "1") (pinfunction "1_1") (pintype "passive"))
      (node (ref "J1") (pin "10") (pinfunction "12V_10") (pintype "bidirectional"))
      (node (ref "J1") (pin "11") (pinfunction "12V_11") (pintype "bidirectional"))
    )
    (net (code "4") (name "-12V") (class "Default")
      (node (ref "0") (pin "7") (pinfunction "-12V_7") (pintype "bidirectional"))
      (node (ref "1") (pin "7") (pinfunction "-12V_7") (pintype "bidirectional"))
      (node (ref "2") (pin "7") (pinfunction "-12V_7") (pintype "bidirectional"))
      (node (ref "3") (pin "7") (pinfunction "-12V_7") (pintype "bidirectional"))
      (node (ref "4") (pin "7") (pinfunction "-12V_7") (pintype "bidirectional"))
      (node (ref "5") (pin "7") (pinfunction "-12V_7") (pintype "bidirectional"))
      (node (ref "6") (pin "7") (pinfunction "-12V_7") (pintype "bidirectional"))
      (node (ref "7") (pin "7") (pinfunction "-12V_7") (pintype "bidirectional"))
      (node (ref "C12") (pin "1") (pinfunction "1_1") (pintype "passive"))
      (node (ref "C16") (pin "1") (pinfunction "1_1") (pintype "passive"))
      (node (ref "C20") (pin "1") (pinfunction "1_1") (pintype "passive"))
      (node (ref "C24") (pin "1") (pinfunction "1_1") (pintype "passive"))
      (node (ref "C28") (pin "1") (pinfunction "1_1") (pintype "passive"))
      (node (ref "C32") (pin "1") (pinfunction "1_1") (pintype "passive"))
      (node (ref "C4") (pin "1") (pinfunction "1_1") (pintype "passive"))
      (node (ref "C48") (pin "+") (pinfunction "+_+") (pintype "passive"))
      (node (ref "C8") (pin "1") (pinfunction "1_1") (pintype "passive"))
      (node (ref "J1") (pin "14") (pinfunction "-12V_14") (pintype "bidirectional"))
    )
    (net (code "5") (name "A0") (class "Default")
      (node (ref "0") (pin "23") (pinfunction "A0_23") (pintype "bidirectional"))
      (node (ref "1") (pin "23") (pinfunction "A0_23") (pintype "bidirectional"))
      (node (ref "2") (pin "23") (pinfunction "A0_23") (pintype "bidirectional"))
      (node (ref "3") (pin "23") (pinfunction "A0_23") (pintype "bidirectional"))
      (node (ref "4") (pin "23") (pinfunction "A0_23") (pintype "bidirectional"))
      (node (ref "5") (pin "23") (pinfunction "A0_23") (pintype "bidirectional"))
      (node (ref "6") (pin "23") (pinfunction "A0_23") (pintype "bidirectional"))
      (node (ref "7") (pin "23") (pinfunction "A0_23") (pintype "bidirectional"))
      (node (ref "RN10") (pin "7") (pinfunction "7_7") (pintype "passive"))
      (node (ref "RN4") (pin "7") (pinfunction "7_7") (pintype "passive"))
    )
    (net (code "6") (name "A1") (class "Default")
      (node (ref "0") (pin "24") (pinfunction "A1_24") (pintype "bidirectional"))
      (node (ref "1") (pin "24") (pinfunction "A1_24") (pintype "bidirectional"))
      (node (ref "2") (pin "24") (pinfunction "A1_24") (pintype "bidirectional"))
      (node (ref "3") (pin "24") (pinfunction "A1_24") (pintype "bidirectional"))
      (node (ref "4") (pin "24") (pinfunction "A1_24") (pintype "bidirectional"))
      (node (ref "5") (pin "24") (pinfunction "A1_24") (pintype "bidirectional"))
      (node (ref "6") (pin "24") (pinfunction "A1_24") (pintype "bidirectional"))
      (node (ref "7") (pin "24") (pinfunction "A1_24") (pintype "bidirectional"))
      (node (ref "RN1") (pin "7") (pinfunction "7_7") (pintype "passive"))
      (node (ref "RN7") (pin "7") (pinfunction "7_7") (pintype "passive"))
    )
    (net (code "7") (name "A2") (class "Default")
      (node (ref "0") (pin "25") (pinfunction "A2_25") (pintype "bidirectional"))
      (node (ref "1") (pin "25") (pinfunction "A2_25") (pintype "bidirectional"))
      (node (ref "2") (pin "25") (pinfunction "A2_25") (pintype "bidirectional"))
      (node (ref "3") (pin "25") (pinfunction "A2_25") (pintype "bidirectional"))
      (node (ref "4") (pin "25") (pinfunction "A2_25") (pintype "bidirectional"))
      (node (ref "5") (pin "25") (pinfunction "A2_25") (pintype "bidirectional"))
      (node (ref "6") (pin "25") (pinfunction "A2_25") (pintype "bidirectional"))
      (node (ref "7") (pin "25") (pinfunction "A2_25") (pintype "bidirectional"))
      (node (ref "RN10") (pin "8") (pinfunction "8_8") (pintype "passive"))
      (node (ref "RN4") (pin "8") (pinfunction "8_8") (pintype "passive"))
    )
    (net (code "8") (name "A3") (class "Default")
      (node (ref "0") (pin "26") (pinfunction "A3_26") (pintype "bidirectional"))
      (node (ref "1") (pin "26") (pinfunction "A3_26") (pintype "bidirectional"))
      (node (ref "2") (pin "26") (pinfunction "A3_26") (pintype "bidirectional"))
      (node (ref "3") (pin "26") (pinfunction "A3_26") (pintype "bidirectional"))
      (node (ref "4") (pin "26") (pinfunction "A3_26") (pintype "bidirectional"))
      (node (ref "5") (pin "26") (pinfunction "A3_26") (pintype "bidirectional"))
      (node (ref "6") (pin "26") (pinfunction "A3_26") (pintype "bidirectional"))
      (node (ref "7") (pin "26") (pinfunction "A3_26") (pintype "bidirectional"))
      (node (ref "RN1") (pin "8") (pinfunction "8_8") (pintype "passive"))
      (node (ref "RN7") (pin "8") (pinfunction "8_8") (pintype "passive"))
    )
    (net (code "9") (name "A4") (class "Default")
      (node (ref "0") (pin "27") (pinfunction "A4_27") (pintype "bidirectional"))
      (node (ref "1") (pin "27") (pinfunction "A4_27") (pintype "bidirectional"))
      (node (ref "2") (pin "27") (pinfunction "A4_27") (pintype "bidirectional"))
      (node (ref "3") (pin "27") (pinfunction "A4_27") (pintype "bidirectional"))
      (node (ref "4") (pin "27") (pinfunction "A4_27") (pintype "bidirectional"))
      (node (ref "5") (pin "27") (pinfunction "A4_27") (pintype "bidirectional"))
      (node (ref "6") (pin "27") (pinfunction "A4_27") (pintype "bidirectional"))
      (node (ref "7") (pin "27") (pinfunction "A4_27") (pintype "bidirectional"))
      (node (ref "RN10") (pin "9") (pinfunction "9_9") (pintype "passive"))
      (node (ref "RN4") (pin "9") (pinfunction "9_9") (pintype "passive"))
    )
    (net (code "10") (name "A5") (class "Default")
      (node (ref "0") (pin "28") (pinfunction "A5_28") (pintype "bidirectional"))
      (node (ref "1") (pin "28") (pinfunction "A5_28") (pintype "bidirectional"))
      (node (ref "2") (pin "28") (pinfunction "A5_28") (pintype "bidirectional"))
      (node (ref "3") (pin "28") (pinfunction "A5_28") (pintype "bidirectional"))
      (node (ref "4") (pin "28") (pinfunction "A5_28") (pintype "bidirectional"))
      (node (ref "5") (pin "28") (pinfunction "A5_28") (pintype "bidirectional"))
      (node (ref "6") (pin "28") (pinfunction "A5_28") (pintype "bidirectional"))
      (node (ref "7") (pin "28") (pinfunction "A5_28") (pintype "bidirectional"))
      (node (ref "RN1") (pin "9") (pinfunction "9_9") (pintype "passive"))
      (node (ref "RN7") (pin "9") (pinfunction "9_9") (pintype "passive"))
    )
    (net (code "11") (name "A6") (class "Default")
      (node (ref "0") (pin "29") (pinfunction "A6_29") (pintype "bidirectional"))
      (node (ref "1") (pin "29") (pinfunction "A6_29") (pintype "bidirectional"))
      (node (ref "2") (pin "29") (pinfunction "A6_29") (pintype "bidirectional"))
      (node (ref "3") (pin "29") (pinfunction "A6_29") (pintype "bidirectional"))
      (node (ref "4") (pin "29") (pinfunction "A6_29") (pintype "bidirectional"))
      (node (ref "5") (pin "29") (pinfunction "A6_29") (pintype "bidirectional"))
      (node (ref "6") (pin "29") (pinfunction "A6_29") (pintype "bidirectional"))
      (node (ref "7") (pin "29") (pinfunction "A6_29") (pintype "bidirectional"))
      (node (ref "RN11") (pin "2") (pinfunction "2_2") (pintype "passive"))
      (node (ref "RN5") (pin "2") (pinfunction "2_2") (pintype "passive"))
    )
    (net (code "12") (name "A7") (class "Default")
      (node (ref "0") (pin "30") (pinfunction "A7_30") (pintype "bidirectional"))
      (node (ref "1") (pin "30") (pinfunction "A7_30") (pintype "bidirectional"))
      (node (ref "2") (pin "30") (pinfunction "A7_30") (pintype "bidirectional"))
      (node (ref "3") (pin "30") (pinfunction "A7_30") (pintype "bidirectional"))
      (node (ref "4") (pin "30") (pinfunction "A7_30") (pintype "bidirectional"))
      (node (ref "5") (pin "30") (pinfunction "A7_30") (pintype "bidirectional"))
      (node (ref "6") (pin "30") (pinfunction "A7_30") (pintype "bidirectional"))
      (node (ref "7") (pin "30") (pinfunction "A7_30") (pintype "bidirectional"))
      (node (ref "RN2") (pin "2") (pinfunction "2_2") (pintype "passive"))
      (node (ref "RN8") (pin "2") (pinfunction "2_2") (pintype "passive"))
    )
    (net (code "13") (name "A8") (class "Default")
      (node (ref "0") (pin "31") (pinfunction "A8_31") (pintype "bidirectional"))
      (node (ref "1") (pin "31") (pinfunction "A8_31") (pintype "bidirectional"))
      (node (ref "2") (pin "31") (pinfunction "A8_31") (pintype "bidirectional"))
      (node (ref "3") (pin "31") (pinfunction "A8_31") (pintype "bidirectional"))
      (node (ref "4") (pin "31") (pinfunction "A8_31") (pintype "bidirectional"))
      (node (ref "5") (pin "31") (pinfunction "A8_31") (pintype "bidirectional"))
      (node (ref "6") (pin "31") (pinfunction "A8_31") (pintype "bidirectional"))
      (node (ref "7") (pin "31") (pinfunction "A8_31") (pintype "bidirectional"))
      (node (ref "RN11") (pin "3") (pinfunction "3_3") (pintype "passive"))
      (node (ref "RN5") (pin "3") (pinfunction "3_3") (pintype "passive"))
      (node (ref "U7") (pin "1") (pinfunction "A_1") (pintype "input"))
    )
    (net (code "14") (name "A9") (class "Default")
      (node (ref "0") (pin "32") (pinfunction "A9_32") (pintype "bidirectional"))
      (node (ref "1") (pin "32") (pinfunction "A9_32") (pintype "bidirectional"))
      (node (ref "2") (pin "32") (pinfunction "A9_32") (pintype "bidirectional"))
      (node (ref "3") (pin "32") (pinfunction "A9_32") (pintype "bidirectional"))
      (node (ref "4") (pin "32") (pinfunction "A9_32") (pintype "bidirectional"))
      (node (ref "5") (pin "32") (pinfunction "A9_32") (pintype "bidirectional"))
      (node (ref "6") (pin "32") (pinfunction "A9_32") (pintype "bidirectional"))
      (node (ref "7") (pin "32") (pinfunction "A9_32") (pintype "bidirectional"))
      (node (ref "RN2") (pin "3") (pinfunction "3_3") (pintype "passive"))
      (node (ref "RN8") (pin "3") (pinfunction "3_3") (pintype "passive"))
      (node (ref "U7") (pin "2") (pinfunction "B_2") (pintype "input"))
    )
    (net (code "15") (name "A10") (class "Default")
      (node (ref "0") (pin "33") (pinfunction "A10_33") (pintype "bidirectional"))
      (node (ref "1") (pin "33") (pinfunction "A10_33") (pintype "bidirectional"))
      (node (ref "2") (pin "33") (pinfunction "A10_33") (pintype "bidirectional"))
      (node (ref "3") (pin "33") (pinfunction "A10_33") (pintype "bidirectional"))
      (node (ref "4") (pin "33") (pinfunction "A10_33") (pintype "bidirectional"))
      (node (ref "5") (pin "33") (pinfunction "A10_33") (pintype "bidirectional"))
      (node (ref "6") (pin "33") (pinfunction "A10_33") (pintype "bidirectional"))
      (node (ref "7") (pin "33") (pinfunction "A10_33") (pintype "bidirectional"))
      (node (ref "RN11") (pin "4") (pinfunction "4_4") (pintype "passive"))
      (node (ref "RN5") (pin "4") (pinfunction "4_4") (pintype "passive"))
      (node (ref "U7") (pin "3") (pinfunction "C_3") (pintype "input"))
    )
    (net (code "16") (name "A11") (class "Default")
      (node (ref "0") (pin "34") (pinfunction "A11_34") (pintype "bidirectional"))
      (node (ref "1") (pin "34") (pinfunction "A11_34") (pintype "bidirectional"))
      (node (ref "2") (pin "34") (pinfunction "A11_34") (pintype "bidirectional"))
      (node (ref "3") (pin "34") (pinfunction "A11_34") (pintype "bidirectional"))
      (node (ref "4") (pin "34") (pinfunction "A11_34") (pintype "bidirectional"))
      (node (ref "5") (pin "34") (pinfunction "A11_34") (pintype "bidirectional"))
      (node (ref "6") (pin "34") (pinfunction "A11_34") (pintype "bidirectional"))
      (node (ref "7") (pin "34") (pinfunction "A11_34") (pintype "bidirectional"))
      (node (ref "RN2") (pin "4") (pinfunction "4_4") (pintype "passive"))
      (node (ref "RN8") (pin "4") (pinfunction "4_4") (pintype "passive"))
      (node (ref "U7") (pin "4") (pinfunction "G2A_4") (pintype "input"))
    )
    (net (code "17") (name "A12") (class "Default")
      (node (ref "0") (pin "35") (pinfunction "A12_35") (pintype "bidirectional"))
      (node (ref "1") (pin "35") (pinfunction "A12_35") (pintype "bidirectional"))
      (node (ref "2") (pin "35") (pinfunction "A12_35") (pintype "bidirectional"))
      (node (ref "3") (pin "35") (pinfunction "A12_35") (pintype "bidirectional"))
      (node (ref "4") (pin "35") (pinfunction "A12_35") (pintype "bidirectional"))
      (node (ref "5") (pin "35") (pinfunction "A12_35") (pintype "bidirectional"))
      (node (ref "6") (pin "35") (pinfunction "A12_35") (pintype "bidirectional"))
      (node (ref "7") (pin "35") (pinfunction "A12_35") (pintype "bidirectional"))
      (node (ref "RN11") (pin "5") (pinfunction "5_5") (pintype "passive"))
      (node (ref "RN5") (pin "5") (pinfunction "5_5") (pintype "passive"))
      (node (ref "U8") (pin "2") (pinfunction "P0_2") (pintype "input"))
    )
    (net (code "18") (name "A13") (class "Default")
      (node (ref "0") (pin "36") (pinfunction "A13_36") (pintype "bidirectional"))
      (node (ref "1") (pin "36") (pinfunction "A13_36") (pintype "bidirectional"))
      (node (ref "2") (pin "36") (pinfunction "A13_36") (pintype "bidirectional"))
      (node (ref "3") (pin "36") (pinfunction "A13_36") (pintype "bidirectional"))
      (node (ref "4") (pin "36") (pinfunction "A13_36") (pintype "bidirectional"))
      (node (ref "5") (pin "36") (pinfunction "A13_36") (pintype "bidirectional"))
      (node (ref "6") (pin "36") (pinfunction "A13_36") (pintype "bidirectional"))
      (node (ref "7") (pin "36") (pinfunction "A13_36") (pintype "bidirectional"))
      (node (ref "RN2") (pin "5") (pinfunction "5_5") (pintype "passive"))
      (node (ref "RN8") (pin "5") (pinfunction "5_5") (pintype "passive"))
      (node (ref "U8") (pin "17") (pinfunction "P7_17") (pintype "input"))
    )
    (net (code "19") (name "A14") (class "Default")
      (node (ref "0") (pin "37") (pinfunction "A14_37") (pintype "bidirectional"))
      (node (ref "1") (pin "37") (pinfunction "A14_37") (pintype "bidirectional"))
      (node (ref "2") (pin "37") (pinfunction "A14_37") (pintype "bidirectional"))
      (node (ref "3") (pin "37") (pinfunction "A14_37") (pintype "bidirectional"))
      (node (ref "4") (pin "37") (pinfunction "A14_37") (pintype "bidirectional"))
      (node (ref "5") (pin "37") (pinfunction "A14_37") (pintype "bidirectional"))
      (node (ref "6") (pin "37") (pinfunction "A14_37") (pintype "bidirectional"))
      (node (ref "7") (pin "37") (pinfunction "A14_37") (pintype "bidirectional"))
      (node (ref "RN11") (pin "6") (pinfunction "6_6") (pintype "passive"))
      (node (ref "RN5") (pin "6") (pinfunction "6_6") (pintype "passive"))
      (node (ref "U8") (pin "4") (pinfunction "P1_4") (pintype "input"))
    )
    (net (code "20") (name "A15") (class "Default")
      (node (ref "0") (pin "38") (pinfunction "A15_38") (pintype "bidirectional"))
      (node (ref "1") (pin "38") (pinfunction "A15_38") (pintype "bidirectional"))
      (node (ref "2") (pin "38") (pinfunction "A15_38") (pintype "bidirectional"))
      (node (ref "3") (pin "38") (pinfunction "A15_38") (pintype "bidirectional"))
      (node (ref "4") (pin "38") (pinfunction "A15_38") (pintype "bidirectional"))
      (node (ref "5") (pin "38") (pinfunction "A15_38") (pintype "bidirectional"))
      (node (ref "6") (pin "38") (pinfunction "A15_38") (pintype "bidirectional"))
      (node (ref "7") (pin "38") (pinfunction "A15_38") (pintype "bidirectional"))
      (node (ref "RN2") (pin "6") (pinfunction "6_6") (pintype "passive"))
      (node (ref "RN8") (pin "6") (pinfunction "6_6") (pintype "passive"))
      (node (ref "U8") (pin "15") (pinfunction "P6_15") (pintype "input"))
    )
    (net (code "21") (name "A16") (class "Default")
      (node (ref "0") (pin "39") (pinfunction "A16_39") (pintype "bidirectional"))
      (node (ref "1") (pin "39") (pinfunction "A16_39") (pintype "bidirectional"))
      (node (ref "2") (pin "39") (pinfunction "A16_39") (pintype "bidirectional"))
      (node (ref "3") (pin "39") (pinfunction "A16_39") (pintype "bidirectional"))
      (node (ref "4") (pin "39") (pinfunction "A16_39") (pintype "bidirectional"))
      (node (ref "5") (pin "39") (pinfunction "A16_39") (pintype "bidirectional"))
      (node (ref "6") (pin "39") (pinfunction "A16_39") (pintype "bidirectional"))
      (node (ref "7") (pin "39") (pinfunction "A16_39") (pintype "bidirectional"))
      (node (ref "RN11") (pin "7") (pinfunction "7_7") (pintype "passive"))
      (node (ref "RN5") (pin "7") (pinfunction "7_7") (pintype "passive"))
      (node (ref "U8") (pin "6") (pinfunction "P2_6") (pintype "input"))
    )
    (net (code "22") (name "A17") (class "Default")
      (node (ref "0") (pin "40") (pinfunction "A17_40") (pintype "bidirectional"))
      (node (ref "1") (pin "40") (pinfunction "A17_40") (pintype "bidirectional"))
      (node (ref "2") (pin "40") (pinfunction "A17_40") (pintype "bidirectional"))
      (node (ref "3") (pin "40") (pinfunction "A17_40") (pintype "bidirectional"))
      (node (ref "4") (pin "40") (pinfunction "A17_40") (pintype "bidirectional"))
      (node (ref "5") (pin "40") (pinfunction "A17_40") (pintype "bidirectional"))
      (node (ref "6") (pin "40") (pinfunction "A17_40") (pintype "bidirectional"))
      (node (ref "7") (pin "40") (pinfunction "A17_40") (pintype "bidirectional"))
      (node (ref "RN2") (pin "7") (pinfunction "7_7") (pintype "passive"))
      (node (ref "RN8") (pin "7") (pinfunction "7_7") (pintype "passive"))
      (node (ref "U8") (pin "13") (pinfunction "P5_13") (pintype "input"))
    )
    (net (code "23") (name "A18") (class "Default")
      (node (ref "0") (pin "41") (pinfunction "A18_41") (pintype "bidirectional"))
      (node (ref "1") (pin "41") (pinfunction "A18_41") (pintype "bidirectional"))
      (node (ref "2") (pin "41") (pinfunction "A18_41") (pintype "bidirectional"))
      (node (ref "3") (pin "41") (pinfunction "A18_41") (pintype "bidirectional"))
      (node (ref "4") (pin "41") (pinfunction "A18_41") (pintype "bidirectional"))
      (node (ref "5") (pin "41") (pinfunction "A18_41") (pintype "bidirectional"))
      (node (ref "6") (pin "41") (pinfunction "A18_41") (pintype "bidirectional"))
      (node (ref "7") (pin "41") (pinfunction "A18_41") (pintype "bidirectional"))
      (node (ref "RN11") (pin "8") (pinfunction "8_8") (pintype "passive"))
      (node (ref "RN5") (pin "8") (pinfunction "8_8") (pintype "passive"))
      (node (ref "U8") (pin "8") (pinfunction "P3_8") (pintype "input"))
    )
    (net (code "24") (name "A19") (class "Default")
      (node (ref "0") (pin "42") (pinfunction "A19_42") (pintype "bidirectional"))
      (node (ref "1") (pin "42") (pinfunction "A19_42") (pintype "bidirectional"))
      (node (ref "2") (pin "42") (pinfunction "A19_42") (pintype "bidirectional"))
      (node (ref "3") (pin "42") (pinfunction "A19_42") (pintype "bidirectional"))
      (node (ref "4") (pin "42") (pinfunction "A19_42") (pintype "bidirectional"))
      (node (ref "5") (pin "42") (pinfunction "A19_42") (pintype "bidirectional"))
      (node (ref "6") (pin "42") (pinfunction "A19_42") (pintype "bidirectional"))
      (node (ref "7") (pin "42") (pinfunction "A19_42") (pintype "bidirectional"))
      (node (ref "RN2") (pin "8") (pinfunction "8_8") (pintype "passive"))
      (node (ref "RN8") (pin "8") (pinfunction "8_8") (pintype "passive"))
      (node (ref "U8") (pin "11") (pinfunction "P4_11") (pintype "input"))
    )
    (net (code "25") (name "CKLAUX") (class "Default")
      (node (ref "0") (pin "16") (pinfunction "CLKAUX_16") (pintype "bidirectional"))
      (node (ref "1") (pin "16") (pinfunction "CLKAUX_16") (pintype "bidirectional"))
      (node (ref "2") (pin "16") (pinfunction "CLKAUX_16") (pintype "bidirectional"))
      (node (ref "3") (pin "16") (pinfunction "CLKAUX_16") (pintype "bidirectional"))
      (node (ref "4") (pin "16") (pinfunction "CLKAUX_16") (pintype "bidirectional"))
      (node (ref "5") (pin "16") (pinfunction "CLKAUX_16") (pintype "bidirectional"))
      (node (ref "6") (pin "16") (pinfunction "CLKAUX_16") (pintype "bidirectional"))
      (node (ref "7") (pin "16") (pinfunction "CLKAUX_16") (pintype "bidirectional"))
      (node (ref "RN1") (pin "3") (pinfunction "3_3") (pintype "passive"))
      (node (ref "RN7") (pin "3") (pinfunction "3_3") (pintype "passive"))
    )
    (net (code "26") (name "CLK") (class "Default")
      (node (ref "0") (pin "15") (pinfunction "CLK_15") (pintype "bidirectional"))
      (node (ref "1") (pin "15") (pinfunction "CLK_15") (pintype "bidirectional"))
      (node (ref "2") (pin "15") (pinfunction "CLK_15") (pintype "bidirectional"))
      (node (ref "3") (pin "15") (pinfunction "CLK_15") (pintype "bidirectional"))
      (node (ref "4") (pin "15") (pinfunction "CLK_15") (pintype "bidirectional"))
      (node (ref "5") (pin "15") (pinfunction "CLK_15") (pintype "bidirectional"))
      (node (ref "6") (pin "15") (pinfunction "CLK_15") (pintype "bidirectional"))
      (node (ref "7") (pin "15") (pinfunction "CLK_15") (pintype "bidirectional"))
      (node (ref "RN10") (pin "3") (pinfunction "3_3") (pintype "passive"))
      (node (ref "RN4") (pin "3") (pinfunction "3_3") (pintype "passive"))
    )
    (net (code "27") (name "D0") (class "Default")
      (node (ref "0") (pin "43") (pinfunction "D0_43") (pintype "bidirectional"))
      (node (ref "1") (pin "43") (pinfunction "D0_43") (pintype "bidirectional"))
      (node (ref "2") (pin "43") (pinfunction "D0_43") (pintype "bidirectional"))
      (node (ref "3") (pin "43") (pinfunction "D0_43") (pintype "bidirectional"))
      (node (ref "4") (pin "43") (pinfunction "D0_43") (pintype "bidirectional"))
      (node (ref "5") (pin "43") (pinfunction "D0_43") (pintype "bidirectional"))
      (node (ref "6") (pin "43") (pinfunction "D0_43") (pintype "bidirectional"))
      (node (ref "7") (pin "43") (pinfunction "D0_43") (pintype "bidirectional"))
      (node (ref "RN11") (pin "9") (pinfunction "9_9") (pintype "passive"))
      (node (ref "RN5") (pin "9") (pinfunction "9_9") (pintype "passive"))
    )
    (net (code "28") (name "D1") (class "Default")
      (node (ref "0") (pin "44") (pinfunction "D1_44") (pintype "bidirectional"))
      (node (ref "1") (pin "44") (pinfunction "D1_44") (pintype "bidirectional"))
      (node (ref "2") (pin "44") (pinfunction "D1_44") (pintype "bidirectional"))
      (node (ref "3") (pin "44") (pinfunction "D1_44") (pintype "bidirectional"))
      (node (ref "4") (pin "44") (pinfunction "D1_44") (pintype "bidirectional"))
      (node (ref "5") (pin "44") (pinfunction "D1_44") (pintype "bidirectional"))
      (node (ref "6") (pin "44") (pinfunction "D1_44") (pintype "bidirectional"))
      (node (ref "7") (pin "44") (pinfunction "D1_44") (pintype "bidirectional"))
      (node (ref "RN2") (pin "9") (pinfunction "9_9") (pintype "passive"))
      (node (ref "RN8") (pin "9") (pinfunction "9_9") (pintype "passive"))
    )
    (net (code "29") (name "D2") (class "Default")
      (node (ref "0") (pin "45") (pinfunction "D2_45") (pintype "bidirectional"))
      (node (ref "1") (pin "45") (pinfunction "D2_45") (pintype "bidirectional"))
      (node (ref "2") (pin "45") (pinfunction "D2_45") (pintype "bidirectional"))
      (node (ref "3") (pin "45") (pinfunction "D2_45") (pintype "bidirectional"))
      (node (ref "4") (pin "45") (pinfunction "D2_45") (pintype "bidirectional"))
      (node (ref "5") (pin "45") (pinfunction "D2_45") (pintype "bidirectional"))
      (node (ref "6") (pin "45") (pinfunction "D2_45") (pintype "bidirectional"))
      (node (ref "7") (pin "45") (pinfunction "D2_45") (pintype "bidirectional"))
      (node (ref "RN12") (pin "9") (pinfunction "9_9") (pintype "passive"))
      (node (ref "RN6") (pin "9") (pinfunction "9_9") (pintype "passive"))
    )
    (net (code "30") (name "D3") (class "Default")
      (node (ref "0") (pin "46") (pinfunction "D3_46") (pintype "bidirectional"))
      (node (ref "1") (pin "46") (pinfunction "D3_46") (pintype "bidirectional"))
      (node (ref "2") (pin "46") (pinfunction "D3_46") (pintype "bidirectional"))
      (node (ref "3") (pin "46") (pinfunction "D3_46") (pintype "bidirectional"))
      (node (ref "4") (pin "46") (pinfunction "D3_46") (pintype "bidirectional"))
      (node (ref "5") (pin "46") (pinfunction "D3_46") (pintype "bidirectional"))
      (node (ref "6") (pin "46") (pinfunction "D3_46") (pintype "bidirectional"))
      (node (ref "7") (pin "46") (pinfunction "D3_46") (pintype "bidirectional"))
      (node (ref "RN3") (pin "9") (pinfunction "9_9") (pintype "passive"))
      (node (ref "RN9") (pin "9") (pinfunction "9_9") (pintype "passive"))
    )
    (net (code "31") (name "D4") (class "Default")
      (node (ref "0") (pin "47") (pinfunction "D4_47") (pintype "bidirectional"))
      (node (ref "1") (pin "47") (pinfunction "D4_47") (pintype "bidirectional"))
      (node (ref "2") (pin "47") (pinfunction "D4_47") (pintype "bidirectional"))
      (node (ref "3") (pin "47") (pinfunction "D4_47") (pintype "bidirectional"))
      (node (ref "4") (pin "47") (pinfunction "D4_47") (pintype "bidirectional"))
      (node (ref "5") (pin "47") (pinfunction "D4_47") (pintype "bidirectional"))
      (node (ref "6") (pin "47") (pinfunction "D4_47") (pintype "bidirectional"))
      (node (ref "7") (pin "47") (pinfunction "D4_47") (pintype "bidirectional"))
      (node (ref "RN12") (pin "8") (pinfunction "8_8") (pintype "passive"))
      (node (ref "RN6") (pin "8") (pinfunction "8_8") (pintype "passive"))
    )
    (net (code "32") (name "D5") (class "Default")
      (node (ref "0") (pin "48") (pinfunction "D5_48") (pintype "bidirectional"))
      (node (ref "1") (pin "48") (pinfunction "D5_48") (pintype "bidirectional"))
      (node (ref "2") (pin "48") (pinfunction "D5_48") (pintype "bidirectional"))
      (node (ref "3") (pin "48") (pinfunction "D5_48") (pintype "bidirectional"))
      (node (ref "4") (pin "48") (pinfunction "D5_48") (pintype "bidirectional"))
      (node (ref "5") (pin "48") (pinfunction "D5_48") (pintype "bidirectional"))
      (node (ref "6") (pin "48") (pinfunction "D5_48") (pintype "bidirectional"))
      (node (ref "7") (pin "48") (pinfunction "D5_48") (pintype "bidirectional"))
      (node (ref "RN3") (pin "8") (pinfunction "8_8") (pintype "passive"))
      (node (ref "RN9") (pin "8") (pinfunction "8_8") (pintype "passive"))
    )
    (net (code "33") (name "D6") (class "Default")
      (node (ref "0") (pin "49") (pinfunction "D6_49") (pintype "bidirectional"))
      (node (ref "1") (pin "49") (pinfunction "D6_49") (pintype "bidirectional"))
      (node (ref "2") (pin "49") (pinfunction "D6_49") (pintype "bidirectional"))
      (node (ref "3") (pin "49") (pinfunction "D6_49") (pintype "bidirectional"))
      (node (ref "4") (pin "49") (pinfunction "D6_49") (pintype "bidirectional"))
      (node (ref "5") (pin "49") (pinfunction "D6_49") (pintype "bidirectional"))
      (node (ref "6") (pin "49") (pinfunction "D6_49") (pintype "bidirectional"))
      (node (ref "7") (pin "49") (pinfunction "D6_49") (pintype "bidirectional"))
      (node (ref "RN12") (pin "7") (pinfunction "7_7") (pintype "passive"))
      (node (ref "RN6") (pin "7") (pinfunction "7_7") (pintype "passive"))
    )
    (net (code "34") (name "D7") (class "Default")
      (node (ref "0") (pin "50") (pinfunction "D7_50") (pintype "bidirectional"))
      (node (ref "1") (pin "50") (pinfunction "D7_50") (pintype "bidirectional"))
      (node (ref "2") (pin "50") (pinfunction "D7_50") (pintype "bidirectional"))
      (node (ref "3") (pin "50") (pinfunction "D7_50") (pintype "bidirectional"))
      (node (ref "4") (pin "50") (pinfunction "D7_50") (pintype "bidirectional"))
      (node (ref "5") (pin "50") (pinfunction "D7_50") (pintype "bidirectional"))
      (node (ref "6") (pin "50") (pinfunction "D7_50") (pintype "bidirectional"))
      (node (ref "7") (pin "50") (pinfunction "D7_50") (pintype "bidirectional"))
      (node (ref "RN3") (pin "7") (pinfunction "7_7") (pintype "passive"))
      (node (ref "RN9") (pin "7") (pinfunction "7_7") (pintype "passive"))
    )
    (net (code "35") (name "GND") (class "Default")
      (node (ref "0") (pin "3") (pinfunction "GND_3") (pintype "bidirectional"))
      (node (ref "0") (pin "4") (pinfunction "GND_4") (pintype "bidirectional"))
      (node (ref "0") (pin "62") (pinfunction "GND_62") (pintype "bidirectional"))
      (node (ref "1") (pin "3") (pinfunction "GND_3") (pintype "bidirectional"))
      (node (ref "1") (pin "4") (pinfunction "GND_4") (pintype "bidirectional"))
      (node (ref "1") (pin "62") (pinfunction "GND_62") (pintype "bidirectional"))
      (node (ref "2") (pin "3") (pinfunction "GND_3") (pintype "bidirectional"))
      (node (ref "2") (pin "4") (pinfunction "GND_4") (pintype "bidirectional"))
      (node (ref "2") (pin "62") (pinfunction "GND_62") (pintype "bidirectional"))
      (node (ref "3") (pin "3") (pinfunction "GND_3") (pintype "bidirectional"))
      (node (ref "3") (pin "4") (pinfunction "GND_4") (pintype "bidirectional"))
      (node (ref "3") (pin "62") (pinfunction "GND_62") (pintype "bidirectional"))
      (node (ref "4") (pin "3") (pinfunction "GND_3") (pintype "bidirectional"))
      (node (ref "4") (pin "4") (pinfunction "GND_4") (pintype "bidirectional"))
      (node (ref "4") (pin "62") (pinfunction "GND_62") (pintype "bidirectional"))
      (node (ref "5") (pin "3") (pinfunction "GND_3") (pintype "bidirectional"))
      (node (ref "5") (pin "4") (pinfunction "GND_4") (pintype "bidirectional"))
      (node (ref "5") (pin "62") (pinfunction "GND_62") (pintype "bidirectional"))
      (node (ref "6") (pin "3") (pinfunction "GND_3") (pintype "bidirectional"))
      (node (ref "6") (pin "4") (pinfunction "GND_4") (pintype "bidirectional"))
      (node (ref "6") (pin "62") (pinfunction "GND_62") (pintype "bidirectional"))
      (node (ref "7") (pin "3") (pinfunction "GND_3") (pintype "bidirectional"))
      (node (ref "7") (pin "4") (pinfunction "GND_4") (pintype "bidirectional"))
      (node (ref "7") (pin "62") (pinfunction "GND_62") (pintype "bidirectional"))
      (node (ref "C1") (pin "2") (pinfunction "2_2") (pintype "passive"))
      (node (ref "C10") (pin "2") (pinfunction "2_2") (pintype "passive"))
      (node (ref "C11") (pin "2") (pinfunction "2_2") (pintype "passive"))
      (node (ref "C12") (pin "2") (pinfunction "2_2") (pintype "passive"))
      (node (ref "C13") (pin "2") (pinfunction "2_2") (pintype "passive"))
      (node (ref "C14") (pin "2") (pinfunction "2_2") (pintype "passive"))
      (node (ref "C15") (pin "2") (pinfunction "2_2") (pintype "passive"))
      (node (ref "C16") (pin "2") (pinfunction "2_2") (pintype "passive"))
      (node (ref "C17") (pin "2") (pinfunction "2_2") (pintype "passive"))
      (node (ref "C18") (pin "2") (pinfunction "2_2") (pintype "passive"))
      (node (ref "C19") (pin "2") (pinfunction "2_2") (pintype "passive"))
      (node (ref "C2") (pin "2") (pinfunction "2_2") (pintype "passive"))
      (node (ref "C20") (pin "2") (pinfunction "2_2") (pintype "passive"))
      (node (ref "C21") (pin "2") (pinfunction "2_2") (pintype "passive"))
      (node (ref "C22") (pin "2") (pinfunction "2_2") (pintype "passive"))
      (node (ref "C23") (pin "2") (pinfunction "2_2") (pintype "passive"))
      (node (ref "C24") (pin "2") (pinfunction "2_2") (pintype "passive"))
      (node (ref "C25") (pin "2") (pinfunction "2_2") (pintype "passive"))
      (node (ref "C26") (pin "2") (pinfunction "2_2") (pintype "passive"))
      (node (ref "C27") (pin "2") (pinfunction "2_2") (pintype "passive"))
      (node (ref "C28") (pin "2") (pinfunction "2_2") (pintype "passive"))
      (node (ref "C29") (pin "2") (pinfunction "2_2") (pintype "passive"))
      (node (ref "C3") (pin "2") (pinfunction "2_2") (pintype "passive"))
      (node (ref "C30") (pin "2") (pinfunction "2_2") (pintype "passive"))
      (node (ref "C31") (pin "2") (pinfunction "2_2") (pintype "passive"))
      (node (ref "C32") (pin "2") (pinfunction "2_2") (pintype "passive"))
      (node (ref "C34") (pin "2") (pinfunction "2_2") (pintype "passive"))
      (node (ref "C35") (pin "2") (pinfunction "2_2") (pintype "passive"))
      (node (ref "C36") (pin "2") (pinfunction "2_2") (pintype "passive"))
      (node (ref "C37") (pin "2") (pinfunction "2_2") (pintype "passive"))
      (node (ref "C38") (pin "2") (pinfunction "2_2") (pintype "passive"))
      (node (ref "C39") (pin "2") (pinfunction "2_2") (pintype "passive"))
      (node (ref "C4") (pin "2") (pinfunction "2_2") (pintype "passive"))
      (node (ref "C40") (pin "2") (pinfunction "2_2") (pintype "passive"))
      (node (ref "C41") (pin "2") (pinfunction "2_2") (pintype "passive"))
      (node (ref "C42") (pin "2") (pinfunction "2_2") (pintype "passive"))
      (node (ref "C43") (pin "2") (pinfunction "2_2") (pintype "passive"))
      (node (ref "C44") (pin "2") (pinfunction "2_2") (pintype "passive"))
      (node (ref "C45") (pin "-") (pinfunction "-_-") (pintype "passive"))
      (node (ref "C46") (pin "2") (pinfunction "2_2") (pintype "passive"))
      (node (ref "C47") (pin "-") (pinfunction "-_-") (pintype "passive"))
      (node (ref "C48") (pin "-") (pinfunction "-_-") (pintype "passive"))
      (node (ref "C49") (pin "-") (pinfunction "-_-") (pintype "passive"))
      (node (ref "C5") (pin "2") (pinfunction "2_2") (pintype "passive"))
      (node (ref "C50") (pin "-") (pinfunction "-_-") (pintype "passive"))
      (node (ref "C51") (pin "-") (pinfunction "-_-") (pintype "passive"))
      (node (ref "C52") (pin "2") (pinfunction "2_2") (pintype "passive"))
      (node (ref "C53") (pin "2") (pinfunction "2_2") (pintype "passive"))
      (node (ref "C54") (pin "2") (pinfunction "2_2") (pintype "passive"))
      (node (ref "C55") (pin "2") (pinfunction "2_2") (pintype "passive"))
      (node (ref "C57") (pin "-") (pinfunction "-_-") (pintype "passive"))
      (node (ref "C6") (pin "2") (pinfunction "2_2") (pintype "passive"))
      (node (ref "C7") (pin "2") (pinfunction "2_2") (pintype "passive"))
      (node (ref "C8") (pin "2") (pinfunction "2_2") (pintype "passive"))
      (node (ref "C9") (pin "2") (pinfunction "2_2") (pintype "passive"))
      (node (ref "D3") (pin "K") (pinfunction "C_K") (pintype "passive"))
      (node (ref "J1") (pin "15") (pinfunction "GND_15") (pintype "bidirectional"))
      (node (ref "J1") (pin "17") (pinfunction "GND_17") (pintype "bidirectional"))
      (node (ref "J1") (pin "18") (pinfunction "GND_18") (pintype "bidirectional"))
      (node (ref "J1") (pin "19") (pinfunction "GND_19") (pintype "bidirectional"))
      (node (ref "J1") (pin "24") (pinfunction "GND_24") (pintype "bidirectional"))
      (node (ref "J1") (pin "3") (pinfunction "GND_3") (pintype "bidirectional"))
      (node (ref "J1") (pin "5") (pinfunction "GND_5") (pintype "bidirectional"))
      (node (ref "J1") (pin "7") (pinfunction "GND_7") (pintype "bidirectional"))
      (node (ref "J2") (pin "2") (pinfunction "2_2") (pintype "passive"))
      (node (ref "JP5") (pin "3") (pinfunction "3_3") (pintype "passive"))
      (node (ref "Q1") (pin "1") (pinfunction "E_1") (pintype "passive"))
      (node (ref "Q3") (pin "1") (pinfunction "E_1") (pintype "passive"))
      (node (ref "R5") (pin "1") (pinfunction "1_1") (pintype "passive"))
      (node (ref "RN15") (pin "1") (pinfunction "1_1") (pintype "passive"))
      (node (ref "S1") (pin "P$1") (pinfunction "P$1_P$1") (pintype "bidirectional"))
      (node (ref "U5") (pin "2") (pinfunction "GND_2") (pintype "passive"))
      (node (ref "U9") (pin "1") (pinfunction "GND_1") (pintype "power_in"))
    )
    (net (code "36") (name "Net-(C34-Pad1)") (class "Default")
      (node (ref "C34") (pin "1") (pinfunction "1_1") (pintype "passive"))
      (node (ref "C35") (pin "1") (pinfunction "1_1") (pintype "passive"))
      (node (ref "C36") (pin "1") (pinfunction "1_1") (pintype "passive"))
      (node (ref "JP1") (pin "2") (pinfunction "2_2") (pintype "passive"))
      (node (ref "R1") (pin "1") (pinfunction "1_1") (pintype "passive"))
      (node (ref "RN1") (pin "1") (pinfunction "1_1") (pintype "passive"))
      (node (ref "RN2") (pin "1") (pinfunction "1_1") (pintype "passive"))
      (node (ref "RN3") (pin "1") (pinfunction "1_1") (pintype "passive"))
      (node (ref "RN4") (pin "1") (pinfunction "1_1") (pintype "passive"))
      (node (ref "RN5") (pin "1") (pinfunction "1_1") (pintype "passive"))
      (node (ref "RN6") (pin "1") (pinfunction "1_1") (pintype "passive"))
    )
    (net (code "37") (name "Net-(C37-Pad1)") (class "Default")
      (node (ref "C37") (pin "1") (pinfunction "1_1") (pintype "passive"))
      (node (ref "C38") (pin "1") (pinfunction "1_1") (pintype "passive"))
      (node (ref "C39") (pin "1") (pinfunction "1_1") (pintype "passive"))
      (node (ref "JP2") (pin "2") (pinfunction "2_2") (pintype "passive"))
      (node (ref "R2") (pin "1") (pinfunction "1_1") (pintype "passive"))
      (node (ref "RN10") (pin "1") (pinfunction "1_1") (pintype "passive"))
      (node (ref "RN11") (pin "1") (pinfunction "1_1") (pintype "passive"))
      (node (ref "RN12") (pin "1") (pinfunction "1_1") (pintype "passive"))
      (node (ref "RN7") (pin "1") (pinfunction "1_1") (pintype "passive"))
      (node (ref "RN8") (pin "1") (pinfunction "1_1") (pintype "passive"))
      (node (ref "RN9") (pin "1") (pinfunction "1_1") (pintype "passive"))
    )
    (net (code "38") (name "Net-(C56-Pad2)") (class "Default")
      (node (ref "C56") (pin "2") (pinfunction "2_2") (pintype "passive"))
      (node (ref "D4") (pin "A") (pinfunction "A_A") (pintype "passive"))
      (node (ref "JP5") (pin "2") (pinfunction "2_2") (pintype "passive"))
    )
    (net (code "39") (name "Net-(D1-PadA)") (class "Default")
      (node (ref "D1") (pin "A") (pinfunction "A_A") (pintype "passive"))
      (node (ref "JP3") (pin "1") (pinfunction "1_1") (pintype "passive"))
    )
    (net (code "40") (name "Net-(D2-C)") (class "Default")
      (node (ref "D2") (pin "K") (pinfunction "C_K") (pintype "passive"))
      (node (ref "JP5") (pin "1") (pinfunction "1_1") (pintype "passive"))
      (node (ref "Q1") (pin "3") (pinfunction "C_3") (pintype "passive"))
      (node (ref "R13") (pin "1") (pinfunction "1_1") (pintype "passive"))
    )
    (net (code "41") (name "Net-(D2-PadA)") (class "Default")
      (node (ref "D2") (pin "A") (pinfunction "A_A") (pintype "passive"))
      (node (ref "R11") (pin "1") (pinfunction "1_1") (pintype "passive"))
    )
    (net (code "42") (name "Net-(D3-PadA)") (class "Default")
      (node (ref "D3") (pin "A") (pinfunction "A_A") (pintype "passive"))
      (node (ref "R12") (pin "1") (pinfunction "1_1") (pintype "passive"))
    )
    (net (code "43") (name "Net-(D4-PadC)") (class "Default")
      (node (ref "D4") (pin "C") (pinfunction "C_C") (pintype "passive"))
      (node (ref "D5") (pin "C") (pinfunction "C_C") (pintype "passive"))
      (node (ref "R9") (pin "1") (pinfunction "1_1") (pintype "passive"))
    )
    (net (code "44") (name "Net-(J1-PS_ON)") (class "Default")
      (node (ref "J1") (pin "16") (pinfunction "PS_ON_16") (pintype "bidirectional"))
      (node (ref "J2") (pin "1") (pinfunction "1_1") (pintype "passive"))
      (node (ref "S1") (pin "P$2") (pinfunction "P$2_P$2") (pintype "bidirectional"))
    )
    (net (code "45") (name "Net-(Q1-B)") (class "Default")
      (node (ref "Q1") (pin "2") (pinfunction "B_2") (pintype "passive"))
      (node (ref "R6") (pin "2") (pinfunction "2_2") (pintype "passive"))
    )
    (net (code "46") (name "Net-(Q2-B)") (class "Default")
      (node (ref "Q2") (pin "2") (pinfunction "B_2") (pintype "passive"))
      (node (ref "R10") (pin "2") (pinfunction "2_2") (pintype "passive"))
    )
    (net (code "47") (name "Net-(Q2-C)") (class "Default")
      (node (ref "Q2") (pin "3") (pinfunction "C_3") (pintype "passive"))
      (node (ref "R12") (pin "2") (pinfunction "2_2") (pintype "passive"))
    )
    (net (code "48") (name "Net-(Q3-B)") (class "Default")
      (node (ref "Q3") (pin "2") (pinfunction "B_2") (pintype "passive"))
      (node (ref "R9") (pin "2") (pinfunction "2_2") (pintype "passive"))
    )
    (net (code "49") (name "Net-(Q3-C)") (class "Default")
      (node (ref "JP7") (pin "1") (pinfunction "1_1") (pintype "passive"))
      (node (ref "Q3") (pin "3") (pinfunction "C_3") (pintype "passive"))
    )
    (net (code "50") (name "Net-(U1A-I0)") (class "Default")
      (node (ref "U1") (pin "1") (pinfunction "I0_1") (pintype "input"))
      (node (ref "U2") (pin "2") (pinfunction "O_2") (pintype "output"))
    )
    (net (code "51") (name "Net-(U1A-O)") (class "Default")
      (node (ref "R3") (pin "1") (pinfunction "1_1") (pintype "passive"))
      (node (ref "U1") (pin "3") (pinfunction "O_3") (pintype "output"))
    )
    (net (code "52") (name "Net-(U2A-I)") (class "Default")
      (node (ref "U2") (pin "1") (pinfunction "I_1") (pintype "input"))
      (node (ref "U3") (pin "8") (pinfunction "O_8") (pintype "output"))
    )
    (net (code "53") (name "Net-(U2B-I)") (class "Default")
      (node (ref "U2") (pin "3") (pinfunction "I_3") (pintype "input"))
      (node (ref "U4") (pin "8") (pinfunction "O_8") (pintype "output"))
    )
    (net (code "54") (name "Net-(U2B-O)") (class "Default")
      (node (ref "R4") (pin "1") (pinfunction "1_1") (pintype "passive"))
      (node (ref "U2") (pin "4") (pinfunction "O_4") (pintype "output"))
    )
    (net (code "55") (name "Net-(U5-VI)") (class "Default")
      (node (ref "C44") (pin "1") (pinfunction "1_1") (pintype "passive"))
      (node (ref "D1") (pin "C") (pinfunction "C_C") (pintype "passive"))
      (node (ref "U5") (pin "1") (pinfunction "VI_1") (pintype "input"))
    )
    (net (code "56") (name "Net-(U5-VO)") (class "Default")
      (node (ref "C45") (pin "+") (pinfunction "+_+") (pintype "passive"))
      (node (ref "C46") (pin "1") (pinfunction "1_1") (pintype "passive"))
      (node (ref "JP1") (pin "3") (pinfunction "3_3") (pintype "passive"))
      (node (ref "JP2") (pin "3") (pinfunction "3_3") (pintype "passive"))
      (node (ref "U5") (pin "3") (pinfunction "VO_3") (pintype "passive"))
    )
    (net (code "57") (name "Net-(U8A-G)") (class "Default")
      (node (ref "JP4") (pin "2") (pinfunction "2_2") (pintype "passive"))
      (node (ref "R5") (pin "2") (pinfunction "2_2") (pintype "passive"))
      (node (ref "U8") (pin "1") (pinfunction "G_1") (pintype "input"))
    )
    (net (code "58") (name "Net-(U8A-Q0)") (class "Default")
      (node (ref "RN15") (pin "9") (pinfunction "9_9") (pintype "passive"))
      (node (ref "S2") (pin "9") (pinfunction "9_9") (pintype "passive"))
      (node (ref "U8") (pin "3") (pinfunction "Q0_3") (pintype "input"))
    )
    (net (code "59") (name "Net-(U8A-Q1)") (class "Default")
      (node (ref "RN15") (pin "7") (pinfunction "7_7") (pintype "passive"))
      (node (ref "S2") (pin "11") (pinfunction "11_11") (pintype "passive"))
      (node (ref "U8") (pin "5") (pinfunction "Q1_5") (pintype "input"))
    )
    (net (code "60") (name "Net-(U8A-Q2)") (class "Default")
      (node (ref "RN15") (pin "5") (pinfunction "5_5") (pintype "passive"))
      (node (ref "S2") (pin "13") (pinfunction "13_13") (pintype "passive"))
      (node (ref "U8") (pin "7") (pinfunction "Q2_7") (pintype "input"))
    )
    (net (code "61") (name "Net-(U8A-Q3)") (class "Default")
      (node (ref "RN15") (pin "3") (pinfunction "3_3") (pintype "passive"))
      (node (ref "S2") (pin "15") (pinfunction "15_15") (pintype "passive"))
      (node (ref "U8") (pin "9") (pinfunction "Q3_9") (pintype "input"))
    )
    (net (code "62") (name "Net-(U8A-Q4)") (class "Default")
      (node (ref "RN15") (pin "2") (pinfunction "2_2") (pintype "passive"))
      (node (ref "S2") (pin "16") (pinfunction "16_16") (pintype "passive"))
      (node (ref "U8") (pin "12") (pinfunction "Q4_12") (pintype "input"))
    )
    (net (code "63") (name "Net-(U8A-Q5)") (class "Default")
      (node (ref "RN15") (pin "4") (pinfunction "4_4") (pintype "passive"))
      (node (ref "S2") (pin "14") (pinfunction "14_14") (pintype "passive"))
      (node (ref "U8") (pin "14") (pinfunction "Q5_14") (pintype "input"))
    )
    (net (code "64") (name "Net-(U8A-Q6)") (class "Default")
      (node (ref "RN15") (pin "6") (pinfunction "6_6") (pintype "passive"))
      (node (ref "S2") (pin "12") (pinfunction "12_12") (pintype "passive"))
      (node (ref "U8") (pin "16") (pinfunction "Q6_16") (pintype "input"))
    )
    (net (code "65") (name "Net-(U8A-Q7)") (class "Default")
      (node (ref "RN15") (pin "8") (pinfunction "8_8") (pintype "passive"))
      (node (ref "S2") (pin "10") (pinfunction "10_10") (pintype "passive"))
      (node (ref "U8") (pin "18") (pinfunction "Q7_18") (pintype "input"))
    )
    (net (code "66") (name "Net-(U9-CON)") (class "Default")
      (node (ref "C55") (pin "1") (pinfunction "1_1") (pintype "passive"))
      (node (ref "U9") (pin "5") (pinfunction "CON_5") (pintype "input"))
    )
    (net (code "67") (name "Net-(U9-DIS)") (class "Default")
      (node (ref "C57") (pin "+") (pinfunction "+_+") (pintype "passive"))
      (node (ref "R8") (pin "2") (pinfunction "2_2") (pintype "passive"))
      (node (ref "U9") (pin "6") (pinfunction "TRE_6") (pintype "input"))
      (node (ref "U9") (pin "7") (pinfunction "DIS_7") (pintype "input"))
    )
    (net (code "68") (name "Net-(U9-OUT)") (class "Default")
      (node (ref "D5") (pin "A") (pinfunction "A_A") (pintype "passive"))
      (node (ref "U9") (pin "3") (pinfunction "OUT_3") (pintype "output"))
    )
    (net (code "69") (name "Net-(U9-TRI)") (class "Default")
      (node (ref "C56") (pin "1") (pinfunction "1_1") (pintype "passive"))
      (node (ref "R7") (pin "2") (pinfunction "2_2") (pintype "passive"))
      (node (ref "U9") (pin "2") (pinfunction "TRI_2") (pintype "input"))
    )
    (net (code "70") (name "Net-(U9-VCC+)") (class "Default")
      (node (ref "C54") (pin "1") (pinfunction "1_1") (pintype "passive"))
      (node (ref "JP6") (pin "2") (pinfunction "2_2") (pintype "passive"))
      (node (ref "R11") (pin "2") (pinfunction "2_2") (pintype "passive"))
      (node (ref "R13") (pin "2") (pinfunction "2_2") (pintype "passive"))
      (node (ref "R7") (pin "1") (pinfunction "1_1") (pintype "passive"))
      (node (ref "R8") (pin "1") (pinfunction "1_1") (pintype "passive"))
      (node (ref "U9") (pin "4") (pinfunction "/RES_4") (pintype "input"))
      (node (ref "U9") (pin "8") (pinfunction "VCC+_8") (pintype "power_in"))
    )
    (net (code "71") (name "PG") (class "Default")
      (node (ref "J1") (pin "8") (pinfunction "PWR_OK_8") (pintype "bidirectional"))
      (node (ref "R6") (pin "1") (pinfunction "1_1") (pintype "passive"))
    )
    (net (code "72") (name "VCC") (class "Default")
      (node (ref "0") (pin "5") (pinfunction "+5V_5") (pintype "bidirectional"))
      (node (ref "0") (pin "6") (pinfunction "+5V_6") (pintype "bidirectional"))
      (node (ref "1") (pin "5") (pinfunction "+5V_5") (pintype "bidirectional"))
      (node (ref "1") (pin "6") (pinfunction "+5V_6") (pintype "bidirectional"))
      (node (ref "2") (pin "5") (pinfunction "+5V_5") (pintype "bidirectional"))
      (node (ref "2") (pin "6") (pinfunction "+5V_6") (pintype "bidirectional"))
      (node (ref "3") (pin "5") (pinfunction "+5V_5") (pintype "bidirectional"))
      (node (ref "3") (pin "6") (pinfunction "+5V_6") (pintype "bidirectional"))
      (node (ref "4") (pin "5") (pinfunction "+5V_5") (pintype "bidirectional"))
      (node (ref "4") (pin "6") (pinfunction "+5V_6") (pintype "bidirectional"))
      (node (ref "5") (pin "5") (pinfunction "+5V_5") (pintype "bidirectional"))
      (node (ref "5") (pin "6") (pinfunction "+5V_6") (pintype "bidirectional"))
      (node (ref "6") (pin "5") (pinfunction "+5V_5") (pintype "bidirectional"))
      (node (ref "6") (pin "6") (pinfunction "+5V_6") (pintype "bidirectional"))
      (node (ref "7") (pin "5") (pinfunction "+5V_5") (pintype "bidirectional"))
      (node (ref "7") (pin "6") (pinfunction "+5V_6") (pintype "bidirectional"))
      (node (ref "C10") (pin "1") (pinfunction "1_1") (pintype "passive"))
      (node (ref "C14") (pin "1") (pinfunction "1_1") (pintype "passive"))
      (node (ref "C18") (pin "1") (pinfunction "1_1") (pintype "passive"))
      (node (ref "C2") (pin "1") (pinfunction "1_1") (pintype "passive"))
      (node (ref "C22") (pin "1") (pinfunction "1_1") (pintype "passive"))
      (node (ref "C26") (pin "1") (pinfunction "1_1") (pintype "passive"))
      (node (ref "C30") (pin "1") (pinfunction "1_1") (pintype "passive"))
      (node (ref "C40") (pin "1") (pinfunction "1_1") (pintype "passive"))
      (node (ref "C41") (pin "1") (pinfunction "1_1") (pintype "passive"))
      (node (ref "C42") (pin "1") (pinfunction "1_1") (pintype "passive"))
      (node (ref "C43") (pin "1") (pinfunction "1_1") (pintype "passive"))
      (node (ref "C49") (pin "+") (pinfunction "+_+") (pintype "passive"))
      (node (ref "C52") (pin "1") (pinfunction "1_1") (pintype "passive"))
      (node (ref "C53") (pin "1") (pinfunction "1_1") (pintype "passive"))
      (node (ref "C6") (pin "1") (pinfunction "1_1") (pintype "passive"))
      (node (ref "J1") (pin "21") (pinfunction "5V_21") (pintype "bidirectional"))
      (node (ref "J1") (pin "22") (pinfunction "5V_22") (pintype "bidirectional"))
      (node (ref "J1") (pin "23") (pinfunction "5V_23") (pintype "bidirectional"))
      (node (ref "J1") (pin "4") (pinfunction "5V_4") (pintype "bidirectional"))
      (node (ref "J1") (pin "6") (pinfunction "5V_6") (pintype "bidirectional"))
      (node (ref "JP1") (pin "1") (pinfunction "1_1") (pintype "passive"))
      (node (ref "JP2") (pin "1") (pinfunction "1_1") (pintype "passive"))
      (node (ref "JP3") (pin "2") (pinfunction "2_2") (pintype "passive"))
      (node (ref "JP4") (pin "1") (pinfunction "1_1") (pintype "passive"))
      (node (ref "JP6") (pin "1") (pinfunction "1_1") (pintype "passive"))
      (node (ref "RN13") (pin "1") (pinfunction "1_1") (pintype "passive"))
      (node (ref "RN14") (pin "1") (pinfunction "1_1") (pintype "passive"))
      (node (ref "S2") (pin "1") (pinfunction "1_1") (pintype "passive"))
      (node (ref "S2") (pin "2") (pinfunction "2_2") (pintype "passive"))
      (node (ref "S2") (pin "3") (pinfunction "3_3") (pintype "passive"))
      (node (ref "S2") (pin "4") (pinfunction "4_4") (pintype "passive"))
      (node (ref "S2") (pin "5") (pinfunction "5_5") (pintype "passive"))
      (node (ref "S2") (pin "6") (pinfunction "6_6") (pintype "passive"))
      (node (ref "S2") (pin "7") (pinfunction "7_7") (pintype "passive"))
      (node (ref "S2") (pin "8") (pinfunction "8_8") (pintype "passive"))
      (node (ref "U1") (pin "10") (pinfunction "I1_10") (pintype "input"))
      (node (ref "U1") (pin "12") (pinfunction "I0_12") (pintype "input"))
      (node (ref "U1") (pin "13") (pinfunction "I1_13") (pintype "input"))
      (node (ref "U1") (pin "4") (pinfunction "I0_4") (pintype "input"))
      (node (ref "U1") (pin "5") (pinfunction "I1_5") (pintype "input"))
      (node (ref "U1") (pin "9") (pinfunction "I0_9") (pintype "input"))
      (node (ref "U2") (pin "11") (pinfunction "I_11") (pintype "input"))
      (node (ref "U2") (pin "13") (pinfunction "I_13") (pintype "input"))
      (node (ref "U2") (pin "5") (pinfunction "I_5") (pintype "input"))
      (node (ref "U2") (pin "9") (pinfunction "I_9") (pintype "input"))
      (node (ref "U7") (pin "6") (pinfunction "G1_6") (pintype "input"))
    )
    (net (code "73") (name "unconnected-(J1-3.3V-Pad12)") (class "Default")
      (node (ref "J1") (pin "12") (pinfunction "3.3V_12") (pintype "bidirectional"))
    )
    (net (code "74") (name "unconnected-(J1-NC-Pad20)") (class "Default")
      (node (ref "J1") (pin "20") (pinfunction "NC_20") (pintype "bidirectional"))
    )
    (net (code "75") (name "unconnected-(S1-PadP$3)") (class "Default")
      (node (ref "S1") (pin "P$3") (pinfunction "P$3_P$3") (pintype "bidirectional"))
    )
    (net (code "76") (name "unconnected-(U1B-O-Pad6)") (class "Default")
      (node (ref "U1") (pin "6") (pinfunction "O_6") (pintype "output"))
    )
    (net (code "77") (name "unconnected-(U1C-O-Pad8)") (class "Default")
      (node (ref "U1") (pin "8") (pinfunction "O_8") (pintype "output"))
    )
    (net (code "78") (name "unconnected-(U1D-O-Pad11)") (class "Default")
      (node (ref "U1") (pin "11") (pinfunction "O_11") (pintype "output"))
    )
    (net (code "79") (name "unconnected-(U2C-O-Pad6)") (class "Default")
      (node (ref "U2") (pin "6") (pinfunction "O_6") (pintype "output"))
    )
    (net (code "80") (name "unconnected-(U2D-O-Pad8)") (class "Default")
      (node (ref "U2") (pin "8") (pinfunction "O_8") (pintype "output"))
    )
    (net (code "81") (name "unconnected-(U2E-O-Pad10)") (class "Default")
      (node (ref "U2") (pin "10") (pinfunction "O_10") (pintype "output"))
    )
    (net (code "82") (name "unconnected-(U2F-O-Pad12)") (class "Default")
      (node (ref "U2") (pin "12") (pinfunction "O_12") (pintype "output"))
    )
    (net (code "83") (name "~{BUSACK}") (class "Default")
      (node (ref "0") (pin "20") (pinfunction "~{BUSACK}_20") (pintype "bidirectional"))
      (node (ref "1") (pin "20") (pinfunction "~{BUSACK}_20") (pintype "bidirectional"))
      (node (ref "2") (pin "20") (pinfunction "~{BUSACK}_20") (pintype "bidirectional"))
      (node (ref "3") (pin "20") (pinfunction "~{BUSACK}_20") (pintype "bidirectional"))
      (node (ref "4") (pin "20") (pinfunction "~{BUSACK}_20") (pintype "bidirectional"))
      (node (ref "5") (pin "20") (pinfunction "~{BUSACK}_20") (pintype "bidirectional"))
      (node (ref "6") (pin "20") (pinfunction "~{BUSACK}_20") (pintype "bidirectional"))
      (node (ref "7") (pin "20") (pinfunction "~{BUSACK}_20") (pintype "bidirectional"))
      (node (ref "RN1") (pin "5") (pinfunction "5_5") (pintype "passive"))
      (node (ref "RN7") (pin "5") (pinfunction "5_5") (pintype "passive"))
    )
    (net (code "84") (name "~{BUSRQ0}") (class "Default")
      (node (ref "0") (pin "10") (pinfunction "~{BUSRQ}_10") (pintype "bidirectional"))
      (node (ref "RN14") (pin "2") (pinfunction "2_2") (pintype "passive"))
      (node (ref "U4") (pin "1") (pinfunction "I0_1") (pintype "input"))
    )
    (net (code "85") (name "~{BUSRQ1}") (class "Default")
      (node (ref "1") (pin "10") (pinfunction "~{BUSRQ}_10") (pintype "bidirectional"))
      (node (ref "RN14") (pin "3") (pinfunction "3_3") (pintype "passive"))
      (node (ref "U4") (pin "2") (pinfunction "I1_2") (pintype "input"))
    )
    (net (code "86") (name "~{BUSRQ2}") (class "Default")
      (node (ref "2") (pin "10") (pinfunction "~{BUSRQ}_10") (pintype "bidirectional"))
      (node (ref "RN14") (pin "4") (pinfunction "4_4") (pintype "passive"))
      (node (ref "U4") (pin "3") (pinfunction "I2_3") (pintype "input"))
    )
    (net (code "87") (name "~{BUSRQ3}") (class "Default")
      (node (ref "3") (pin "10") (pinfunction "~{BUSRQ}_10") (pintype "bidirectional"))
      (node (ref "RN14") (pin "5") (pinfunction "5_5") (pintype "passive"))
      (node (ref "U4") (pin "4") (pinfunction "I3_4") (pintype "input"))
    )
    (net (code "88") (name "~{BUSRQ4}") (class "Default")
      (node (ref "4") (pin "10") (pinfunction "~{BUSRQ}_10") (pintype "bidirectional"))
      (node (ref "RN14") (pin "6") (pinfunction "6_6") (pintype "passive"))
      (node (ref "U4") (pin "5") (pinfunction "I4_5") (pintype "input"))
    )
    (net (code "89") (name "~{BUSRQ5}") (class "Default")
      (node (ref "5") (pin "10") (pinfunction "~{BUSRQ}_10") (pintype "bidirectional"))
      (node (ref "RN14") (pin "7") (pinfunction "7_7") (pintype "passive"))
      (node (ref "U4") (pin "6") (pinfunction "I5_6") (pintype "input"))
    )
    (net (code "90") (name "~{BUSRQ6}") (class "Default")
      (node (ref "6") (pin "10") (pinfunction "~{BUSRQ}_10") (pintype "bidirectional"))
      (node (ref "RN14") (pin "8") (pinfunction "8_8") (pintype "passive"))
      (node (ref "U4") (pin "11") (pinfunction "I6_11") (pintype "input"))
    )
    (net (code "91") (name "~{BUSRQ7}") (class "Default")
      (node (ref "7") (pin "10") (pinfunction "~{BUSRQ}_10") (pintype "bidirectional"))
      (node (ref "RN14") (pin "9") (pinfunction "9_9") (pintype "passive"))
      (node (ref "U4") (pin "12") (pinfunction "I7_12") (pintype "input"))
    )
    (net (code "92") (name "~{CBR}") (class "Default")
      (node (ref "0") (pin "12") (pinfunction "~{CBR}_12") (pintype "bidirectional"))
      (node (ref "1") (pin "12") (pinfunction "~{CBR}_12") (pintype "bidirectional"))
      (node (ref "2") (pin "12") (pinfunction "~{CBR}_12") (pintype "bidirectional"))
      (node (ref "3") (pin "12") (pinfunction "~{CBR}_12") (pintype "bidirectional"))
      (node (ref "4") (pin "12") (pinfunction "~{CBR}_12") (pintype "bidirectional"))
      (node (ref "5") (pin "12") (pinfunction "~{CBR}_12") (pintype "bidirectional"))
      (node (ref "6") (pin "12") (pinfunction "~{CBR}_12") (pintype "bidirectional"))
      (node (ref "7") (pin "12") (pinfunction "~{CBR}_12") (pintype "bidirectional"))
      (node (ref "R1") (pin "2") (pinfunction "2_2") (pintype "passive"))
      (node (ref "R2") (pin "2") (pinfunction "2_2") (pintype "passive"))
      (node (ref "R4") (pin "2") (pinfunction "2_2") (pintype "passive"))
    )
    (net (code "93") (name "~{CINH}") (class "Default")
      (node (ref "0") (pin "13") (pinfunction "~{CINH}_13") (pintype "bidirectional"))
      (node (ref "1") (pin "13") (pinfunction "~{CINH}_13") (pintype "bidirectional"))
      (node (ref "2") (pin "13") (pinfunction "~{CINH}_13") (pintype "bidirectional"))
      (node (ref "3") (pin "13") (pinfunction "~{CINH}_13") (pintype "bidirectional"))
      (node (ref "4") (pin "13") (pinfunction "~{CINH}_13") (pintype "bidirectional"))
      (node (ref "5") (pin "13") (pinfunction "~{CINH}_13") (pintype "bidirectional"))
      (node (ref "6") (pin "13") (pinfunction "~{CINH}_13") (pintype "bidirectional"))
      (node (ref "7") (pin "13") (pinfunction "~{CINH}_13") (pintype "bidirectional"))
      (node (ref "R3") (pin "2") (pinfunction "2_2") (pintype "passive"))
      (node (ref "RN10") (pin "2") (pinfunction "2_2") (pintype "passive"))
      (node (ref "RN4") (pin "2") (pinfunction "2_2") (pintype "passive"))
    )
    (net (code "94") (name "~{CS0}") (class "Default")
      (node (ref "0") (pin "9") (pinfunction "~{CSX}_9") (pintype "bidirectional"))
      (node (ref "U7") (pin "15") (pinfunction "Y0_15") (pintype "output"))
    )
    (net (code "95") (name "~{CS1}") (class "Default")
      (node (ref "1") (pin "9") (pinfunction "~{CSX}_9") (pintype "bidirectional"))
      (node (ref "U7") (pin "14") (pinfunction "Y1_14") (pintype "output"))
    )
    (net (code "96") (name "~{CS2}") (class "Default")
      (node (ref "2") (pin "9") (pinfunction "~{CSX}_9") (pintype "bidirectional"))
      (node (ref "U7") (pin "13") (pinfunction "Y2_13") (pintype "output"))
    )
    (net (code "97") (name "~{CS3}") (class "Default")
      (node (ref "3") (pin "9") (pinfunction "~{CSX}_9") (pintype "bidirectional"))
      (node (ref "U7") (pin "12") (pinfunction "Y3_12") (pintype "output"))
    )
    (net (code "98") (name "~{CS4}") (class "Default")
      (node (ref "4") (pin "9") (pinfunction "~{CSX}_9") (pintype "bidirectional"))
      (node (ref "U7") (pin "11") (pinfunction "Y4_11") (pintype "output"))
    )
    (net (code "99") (name "~{CS5}") (class "Default")
      (node (ref "5") (pin "9") (pinfunction "~{CSX}_9") (pintype "bidirectional"))
      (node (ref "U7") (pin "10") (pinfunction "Y5_10") (pintype "output"))
    )
    (net (code "100") (name "~{CS6}") (class "Default")
      (node (ref "6") (pin "9") (pinfunction "~{CSX}_9") (pintype "bidirectional"))
      (node (ref "U7") (pin "9") (pinfunction "Y6_9") (pintype "output"))
    )
    (net (code "101") (name "~{CS7}") (class "Default")
      (node (ref "7") (pin "9") (pinfunction "~{CSX}_9") (pintype "bidirectional"))
      (node (ref "U7") (pin "7") (pinfunction "Y7_7") (pintype "output"))
    )
    (net (code "102") (name "~{FETCH}") (class "Default")
      (node (ref "0") (pin "19") (pinfunction "~{FETCH}_19") (pintype "bidirectional"))
      (node (ref "1") (pin "19") (pinfunction "~{FETCH}_19") (pintype "bidirectional"))
      (node (ref "2") (pin "19") (pinfunction "~{FETCH}_19") (pintype "bidirectional"))
      (node (ref "3") (pin "19") (pinfunction "~{FETCH}_19") (pintype "bidirectional"))
      (node (ref "4") (pin "19") (pinfunction "~{FETCH}_19") (pintype "bidirectional"))
      (node (ref "5") (pin "19") (pinfunction "~{FETCH}_19") (pintype "bidirectional"))
      (node (ref "6") (pin "19") (pinfunction "~{FETCH}_19") (pintype "bidirectional"))
      (node (ref "7") (pin "19") (pinfunction "~{FETCH}_19") (pintype "bidirectional"))
      (node (ref "RN10") (pin "5") (pinfunction "5_5") (pintype "passive"))
      (node (ref "RN4") (pin "5") (pinfunction "5_5") (pintype "passive"))
    )
    (net (code "103") (name "~{HALT}") (class "Default")
      (node (ref "0") (pin "17") (pinfunction "~{HALT}_17") (pintype "bidirectional"))
      (node (ref "1") (pin "17") (pinfunction "~{HALT}_17") (pintype "bidirectional"))
      (node (ref "2") (pin "17") (pinfunction "~{HALT}_17") (pintype "bidirectional"))
      (node (ref "3") (pin "17") (pinfunction "~{HALT}_17") (pintype "bidirectional"))
      (node (ref "4") (pin "17") (pinfunction "~{HALT}_17") (pintype "bidirectional"))
      (node (ref "5") (pin "17") (pinfunction "~{HALT}_17") (pintype "bidirectional"))
      (node (ref "6") (pin "17") (pinfunction "~{HALT}_17") (pintype "bidirectional"))
      (node (ref "7") (pin "17") (pinfunction "~{HALT}_17") (pintype "bidirectional"))
      (node (ref "RN10") (pin "4") (pinfunction "4_4") (pintype "passive"))
      (node (ref "RN4") (pin "4") (pinfunction "4_4") (pintype "passive"))
    )
    (net (code "104") (name "~{INH0}") (class "Default")
      (node (ref "0") (pin "11") (pinfunction "~{INH}_11") (pintype "bidirectional"))
      (node (ref "RN13") (pin "2") (pinfunction "2_2") (pintype "passive"))
      (node (ref "U3") (pin "1") (pinfunction "I0_1") (pintype "input"))
    )
    (net (code "105") (name "~{INH1}") (class "Default")
      (node (ref "1") (pin "11") (pinfunction "~{INH}_11") (pintype "bidirectional"))
      (node (ref "RN13") (pin "3") (pinfunction "3_3") (pintype "passive"))
      (node (ref "U3") (pin "2") (pinfunction "I1_2") (pintype "input"))
    )
    (net (code "106") (name "~{INH2}") (class "Default")
      (node (ref "2") (pin "11") (pinfunction "~{INH}_11") (pintype "bidirectional"))
      (node (ref "RN13") (pin "4") (pinfunction "4_4") (pintype "passive"))
      (node (ref "U3") (pin "3") (pinfunction "I2_3") (pintype "input"))
    )
    (net (code "107") (name "~{INH3}") (class "Default")
      (node (ref "3") (pin "11") (pinfunction "~{INH}_11") (pintype "bidirectional"))
      (node (ref "RN13") (pin "5") (pinfunction "5_5") (pintype "passive"))
      (node (ref "U3") (pin "4") (pinfunction "I3_4") (pintype "input"))
    )
    (net (code "108") (name "~{INH4}") (class "Default")
      (node (ref "4") (pin "11") (pinfunction "~{INH}_11") (pintype "bidirectional"))
      (node (ref "RN13") (pin "6") (pinfunction "6_6") (pintype "passive"))
      (node (ref "U3") (pin "5") (pinfunction "I4_5") (pintype "input"))
    )
    (net (code "109") (name "~{INH5}") (class "Default")
      (node (ref "5") (pin "11") (pinfunction "~{INH}_11") (pintype "bidirectional"))
      (node (ref "RN13") (pin "7") (pinfunction "7_7") (pintype "passive"))
      (node (ref "U3") (pin "6") (pinfunction "I5_6") (pintype "input"))
    )
    (net (code "110") (name "~{INH6}") (class "Default")
      (node (ref "6") (pin "11") (pinfunction "~{INH}_11") (pintype "bidirectional"))
      (node (ref "RN13") (pin "8") (pinfunction "8_8") (pintype "passive"))
      (node (ref "U3") (pin "11") (pinfunction "I6_11") (pintype "input"))
    )
    (net (code "111") (name "~{INH7}") (class "Default")
      (node (ref "7") (pin "11") (pinfunction "~{INH}_11") (pintype "bidirectional"))
      (node (ref "RN13") (pin "9") (pinfunction "9_9") (pintype "passive"))
      (node (ref "U3") (pin "12") (pinfunction "I7_12") (pintype "input"))
    )
    (net (code "112") (name "~{INHPCS}") (class "Default")
      (node (ref "U1") (pin "2") (pinfunction "I1_2") (pintype "input"))
      (node (ref "U7") (pin "5") (pinfunction "G2B_5") (pintype "input"))
      (node (ref "U8") (pin "19") (pinfunction "P=Q_19") (pintype "output"))
    )
    (net (code "113") (name "~{INT}") (class "Default")
      (node (ref "0") (pin "51") (pinfunction "~{INT}_51") (pintype "bidirectional"))
      (node (ref "1") (pin "51") (pinfunction "~{INT}_51") (pintype "bidirectional"))
      (node (ref "2") (pin "51") (pinfunction "~{INT}_51") (pintype "bidirectional"))
      (node (ref "3") (pin "51") (pinfunction "~{INT}_51") (pintype "bidirectional"))
      (node (ref "4") (pin "51") (pinfunction "~{INT}_51") (pintype "bidirectional"))
      (node (ref "5") (pin "51") (pinfunction "~{INT}_51") (pintype "bidirectional"))
      (node (ref "6") (pin "51") (pinfunction "~{INT}_51") (pintype "bidirectional"))
      (node (ref "7") (pin "51") (pinfunction "~{INT}_51") (pintype "bidirectional"))
      (node (ref "RN12") (pin "6") (pinfunction "6_6") (pintype "passive"))
      (node (ref "RN6") (pin "6") (pinfunction "6_6") (pintype "passive"))
    )
    (net (code "114") (name "~{IRQ0}") (class "Default")
      (node (ref "0") (pin "52") (pinfunction "~{IRQX}_52") (pintype "bidirectional"))
      (node (ref "0") (pin "53") (pinfunction "~{IRQ0}_53") (pintype "bidirectional"))
      (node (ref "1") (pin "53") (pinfunction "~{IRQ0}_53") (pintype "bidirectional"))
      (node (ref "2") (pin "53") (pinfunction "~{IRQ0}_53") (pintype "bidirectional"))
      (node (ref "3") (pin "53") (pinfunction "~{IRQ0}_53") (pintype "bidirectional"))
      (node (ref "4") (pin "53") (pinfunction "~{IRQ0}_53") (pintype "bidirectional"))
      (node (ref "5") (pin "53") (pinfunction "~{IRQ0}_53") (pintype "bidirectional"))
      (node (ref "6") (pin "53") (pinfunction "~{IRQ0}_53") (pintype "bidirectional"))
      (node (ref "7") (pin "53") (pinfunction "~{IRQ0}_53") (pintype "bidirectional"))
      (node (ref "RN3") (pin "6") (pinfunction "6_6") (pintype "passive"))
      (node (ref "RN9") (pin "6") (pinfunction "6_6") (pintype "passive"))
    )
    (net (code "115") (name "~{IRQ1}") (class "Default")
      (node (ref "0") (pin "54") (pinfunction "~{IRQ1}_54") (pintype "bidirectional"))
      (node (ref "1") (pin "52") (pinfunction "~{IRQX}_52") (pintype "bidirectional"))
      (node (ref "1") (pin "54") (pinfunction "~{IRQ1}_54") (pintype "bidirectional"))
      (node (ref "2") (pin "54") (pinfunction "~{IRQ1}_54") (pintype "bidirectional"))
      (node (ref "3") (pin "54") (pinfunction "~{IRQ1}_54") (pintype "bidirectional"))
      (node (ref "4") (pin "54") (pinfunction "~{IRQ1}_54") (pintype "bidirectional"))
      (node (ref "5") (pin "54") (pinfunction "~{IRQ1}_54") (pintype "bidirectional"))
      (node (ref "6") (pin "54") (pinfunction "~{IRQ1}_54") (pintype "bidirectional"))
      (node (ref "7") (pin "54") (pinfunction "~{IRQ1}_54") (pintype "bidirectional"))
      (node (ref "RN12") (pin "5") (pinfunction "5_5") (pintype "passive"))
      (node (ref "RN6") (pin "5") (pinfunction "5_5") (pintype "passive"))
    )
    (net (code "116") (name "~{IRQ2}") (class "Default")
      (node (ref "0") (pin "55") (pinfunction "~{IRQ2}_55") (pintype "bidirectional"))
      (node (ref "1") (pin "55") (pinfunction "~{IRQ2}_55") (pintype "bidirectional"))
      (node (ref "2") (pin "52") (pinfunction "~{IRQX}_52") (pintype "bidirectional"))
      (node (ref "2") (pin "55") (pinfunction "~{IRQ2}_55") (pintype "bidirectional"))
      (node (ref "3") (pin "55") (pinfunction "~{IRQ2}_55") (pintype "bidirectional"))
      (node (ref "4") (pin "55") (pinfunction "~{IRQ2}_55") (pintype "bidirectional"))
      (node (ref "5") (pin "55") (pinfunction "~{IRQ2}_55") (pintype "bidirectional"))
      (node (ref "6") (pin "55") (pinfunction "~{IRQ2}_55") (pintype "bidirectional"))
      (node (ref "7") (pin "55") (pinfunction "~{IRQ2}_55") (pintype "bidirectional"))
      (node (ref "RN3") (pin "5") (pinfunction "5_5") (pintype "passive"))
      (node (ref "RN9") (pin "5") (pinfunction "5_5") (pintype "passive"))
    )
    (net (code "117") (name "~{IRQ3}") (class "Default")
      (node (ref "0") (pin "56") (pinfunction "~{IRQ3}_56") (pintype "bidirectional"))
      (node (ref "1") (pin "56") (pinfunction "~{IRQ3}_56") (pintype "bidirectional"))
      (node (ref "2") (pin "56") (pinfunction "~{IRQ3}_56") (pintype "bidirectional"))
      (node (ref "3") (pin "52") (pinfunction "~{IRQX}_52") (pintype "bidirectional"))
      (node (ref "3") (pin "56") (pinfunction "~{IRQ3}_56") (pintype "bidirectional"))
      (node (ref "4") (pin "56") (pinfunction "~{IRQ3}_56") (pintype "bidirectional"))
      (node (ref "5") (pin "56") (pinfunction "~{IRQ3}_56") (pintype "bidirectional"))
      (node (ref "6") (pin "56") (pinfunction "~{IRQ3}_56") (pintype "bidirectional"))
      (node (ref "7") (pin "56") (pinfunction "~{IRQ3}_56") (pintype "bidirectional"))
      (node (ref "RN12") (pin "4") (pinfunction "4_4") (pintype "passive"))
      (node (ref "RN6") (pin "4") (pinfunction "4_4") (pintype "passive"))
    )
    (net (code "118") (name "~{IRQ4}") (class "Default")
      (node (ref "0") (pin "57") (pinfunction "~{IRQ4}_57") (pintype "bidirectional"))
      (node (ref "1") (pin "57") (pinfunction "~{IRQ4}_57") (pintype "bidirectional"))
      (node (ref "2") (pin "57") (pinfunction "~{IRQ4}_57") (pintype "bidirectional"))
      (node (ref "3") (pin "57") (pinfunction "~{IRQ4}_57") (pintype "bidirectional"))
      (node (ref "4") (pin "52") (pinfunction "~{IRQX}_52") (pintype "bidirectional"))
      (node (ref "4") (pin "57") (pinfunction "~{IRQ4}_57") (pintype "bidirectional"))
      (node (ref "5") (pin "57") (pinfunction "~{IRQ4}_57") (pintype "bidirectional"))
      (node (ref "6") (pin "57") (pinfunction "~{IRQ4}_57") (pintype "bidirectional"))
      (node (ref "7") (pin "57") (pinfunction "~{IRQ4}_57") (pintype "bidirectional"))
      (node (ref "RN3") (pin "4") (pinfunction "4_4") (pintype "passive"))
      (node (ref "RN9") (pin "4") (pinfunction "4_4") (pintype "passive"))
    )
    (net (code "119") (name "~{IRQ5}") (class "Default")
      (node (ref "0") (pin "58") (pinfunction "~{IRQ5}_58") (pintype "bidirectional"))
      (node (ref "1") (pin "58") (pinfunction "~{IRQ5}_58") (pintype "bidirectional"))
      (node (ref "2") (pin "58") (pinfunction "~{IRQ5}_58") (pintype "bidirectional"))
      (node (ref "3") (pin "58") (pinfunction "~{IRQ5}_58") (pintype "bidirectional"))
      (node (ref "4") (pin "58") (pinfunction "~{IRQ5}_58") (pintype "bidirectional"))
      (node (ref "5") (pin "52") (pinfunction "~{IRQX}_52") (pintype "bidirectional"))
      (node (ref "5") (pin "58") (pinfunction "~{IRQ5}_58") (pintype "bidirectional"))
      (node (ref "6") (pin "58") (pinfunction "~{IRQ5}_58") (pintype "bidirectional"))
      (node (ref "7") (pin "58") (pinfunction "~{IRQ5}_58") (pintype "bidirectional"))
      (node (ref "RN12") (pin "3") (pinfunction "3_3") (pintype "passive"))
      (node (ref "RN6") (pin "3") (pinfunction "3_3") (pintype "passive"))
    )
    (net (code "120") (name "~{IRQ6}") (class "Default")
      (node (ref "0") (pin "59") (pinfunction "~{IRQ6}_59") (pintype "bidirectional"))
      (node (ref "1") (pin "59") (pinfunction "~{IRQ6}_59") (pintype "bidirectional"))
      (node (ref "2") (pin "59") (pinfunction "~{IRQ6}_59") (pintype "bidirectional"))
      (node (ref "3") (pin "59") (pinfunction "~{IRQ6}_59") (pintype "bidirectional"))
      (node (ref "4") (pin "59") (pinfunction "~{IRQ6}_59") (pintype "bidirectional"))
      (node (ref "5") (pin "59") (pinfunction "~{IRQ6}_59") (pintype "bidirectional"))
      (node (ref "6") (pin "52") (pinfunction "~{IRQX}_52") (pintype "bidirectional"))
      (node (ref "6") (pin "59") (pinfunction "~{IRQ6}_59") (pintype "bidirectional"))
      (node (ref "7") (pin "59") (pinfunction "~{IRQ6}_59") (pintype "bidirectional"))
      (node (ref "RN3") (pin "3") (pinfunction "3_3") (pintype "passive"))
      (node (ref "RN9") (pin "3") (pinfunction "3_3") (pintype "passive"))
    )
    (net (code "121") (name "~{IRQ7}") (class "Default")
      (node (ref "0") (pin "60") (pinfunction "~{IRQ7}_60") (pintype "bidirectional"))
      (node (ref "1") (pin "60") (pinfunction "~{IRQ7}_60") (pintype "bidirectional"))
      (node (ref "2") (pin "60") (pinfunction "~{IRQ7}_60") (pintype "bidirectional"))
      (node (ref "3") (pin "60") (pinfunction "~{IRQ7}_60") (pintype "bidirectional"))
      (node (ref "4") (pin "60") (pinfunction "~{IRQ7}_60") (pintype "bidirectional"))
      (node (ref "5") (pin "60") (pinfunction "~{IRQ7}_60") (pintype "bidirectional"))
      (node (ref "6") (pin "60") (pinfunction "~{IRQ7}_60") (pintype "bidirectional"))
      (node (ref "7") (pin "52") (pinfunction "~{IRQX}_52") (pintype "bidirectional"))
      (node (ref "7") (pin "60") (pinfunction "~{IRQ7}_60") (pintype "bidirectional"))
      (node (ref "RN12") (pin "2") (pinfunction "2_2") (pintype "passive"))
      (node (ref "RN6") (pin "2") (pinfunction "2_2") (pintype "passive"))
    )
    (net (code "122") (name "~{NMI}") (class "Default")
      (node (ref "0") (pin "61") (pinfunction "~{NMI}_61") (pintype "bidirectional"))
      (node (ref "1") (pin "61") (pinfunction "~{NMI}_61") (pintype "bidirectional"))
      (node (ref "2") (pin "61") (pinfunction "~{NMI}_61") (pintype "bidirectional"))
      (node (ref "3") (pin "61") (pinfunction "~{NMI}_61") (pintype "bidirectional"))
      (node (ref "4") (pin "61") (pinfunction "~{NMI}_61") (pintype "bidirectional"))
      (node (ref "5") (pin "61") (pinfunction "~{NMI}_61") (pintype "bidirectional"))
      (node (ref "6") (pin "61") (pinfunction "~{NMI}_61") (pintype "bidirectional"))
      (node (ref "7") (pin "61") (pinfunction "~{NMI}_61") (pintype "bidirectional"))
      (node (ref "RN3") (pin "2") (pinfunction "2_2") (pintype "passive"))
      (node (ref "RN9") (pin "2") (pinfunction "2_2") (pintype "passive"))
    )
    (net (code "123") (name "~{RD}") (class "Default")
      (node (ref "0") (pin "21") (pinfunction "~{RD}_21") (pintype "bidirectional"))
      (node (ref "1") (pin "21") (pinfunction "~{RD}_21") (pintype "bidirectional"))
      (node (ref "2") (pin "21") (pinfunction "~{RD}_21") (pintype "bidirectional"))
      (node (ref "3") (pin "21") (pinfunction "~{RD}_21") (pintype "bidirectional"))
      (node (ref "4") (pin "21") (pinfunction "~{RD}_21") (pintype "bidirectional"))
      (node (ref "5") (pin "21") (pinfunction "~{RD}_21") (pintype "bidirectional"))
      (node (ref "6") (pin "21") (pinfunction "~{RD}_21") (pintype "bidirectional"))
      (node (ref "7") (pin "21") (pinfunction "~{RD}_21") (pintype "bidirectional"))
      (node (ref "RN10") (pin "6") (pinfunction "6_6") (pintype "passive"))
      (node (ref "RN4") (pin "6") (pinfunction "6_6") (pintype "passive"))
    )
    (net (code "124") (name "~{RST}") (class "Default")
      (node (ref "0") (pin "14") (pinfunction "~{RST}_14") (pintype "bidirectional"))
      (node (ref "1") (pin "14") (pinfunction "~{RST}_14") (pintype "bidirectional"))
      (node (ref "2") (pin "14") (pinfunction "~{RST}_14") (pintype "bidirectional"))
      (node (ref "3") (pin "14") (pinfunction "~{RST}_14") (pintype "bidirectional"))
      (node (ref "4") (pin "14") (pinfunction "~{RST}_14") (pintype "bidirectional"))
      (node (ref "5") (pin "14") (pinfunction "~{RST}_14") (pintype "bidirectional"))
      (node (ref "6") (pin "14") (pinfunction "~{RST}_14") (pintype "bidirectional"))
      (node (ref "7") (pin "14") (pinfunction "~{RST}_14") (pintype "bidirectional"))
      (node (ref "JP7") (pin "2") (pinfunction "2_2") (pintype "passive"))
      (node (ref "R10") (pin "1") (pinfunction "1_1") (pintype "passive"))
      (node (ref "RN1") (pin "2") (pinfunction "2_2") (pintype "passive"))
      (node (ref "RN7") (pin "2") (pinfunction "2_2") (pintype "passive"))
    )
    (net (code "125") (name "~{WAIT}") (class "Default")
      (node (ref "0") (pin "18") (pinfunction "~{WAIT}_18") (pintype "bidirectional"))
      (node (ref "1") (pin "18") (pinfunction "~{WAIT}_18") (pintype "bidirectional"))
      (node (ref "2") (pin "18") (pinfunction "~{WAIT}_18") (pintype "bidirectional"))
      (node (ref "3") (pin "18") (pinfunction "~{WAIT}_18") (pintype "bidirectional"))
      (node (ref "4") (pin "18") (pinfunction "~{WAIT}_18") (pintype "bidirectional"))
      (node (ref "5") (pin "18") (pinfunction "~{WAIT}_18") (pintype "bidirectional"))
      (node (ref "6") (pin "18") (pinfunction "~{WAIT}_18") (pintype "bidirectional"))
      (node (ref "7") (pin "18") (pinfunction "~{WAIT}_18") (pintype "bidirectional"))
      (node (ref "RN1") (pin "4") (pinfunction "4_4") (pintype "passive"))
      (node (ref "RN7") (pin "4") (pinfunction "4_4") (pintype "passive"))
    )
    (net (code "126") (name "~{WR}") (class "Default")
      (node (ref "0") (pin "22") (pinfunction "~{WR}_22") (pintype "bidirectional"))
      (node (ref "1") (pin "22") (pinfunction "~{WR}_22") (pintype "bidirectional"))
      (node (ref "2") (pin "22") (pinfunction "~{WR}_22") (pintype "bidirectional"))
      (node (ref "3") (pin "22") (pinfunction "~{WR}_22") (pintype "bidirectional"))
      (node (ref "4") (pin "22") (pinfunction "~{WR}_22") (pintype "bidirectional"))
      (node (ref "5") (pin "22") (pinfunction "~{WR}_22") (pintype "bidirectional"))
      (node (ref "6") (pin "22") (pinfunction "~{WR}_22") (pintype "bidirectional"))
      (node (ref "7") (pin "22") (pinfunction "~{WR}_22") (pintype "bidirectional"))
      (node (ref "RN1") (pin "6") (pinfunction "6_6") (pintype "passive"))
      (node (ref "RN7") (pin "6") (pinfunction "6_6") (pintype "passive"))
    )
  )
)
